# poseidon.net
KiCad netlist of a schematic drawn in EAGLE
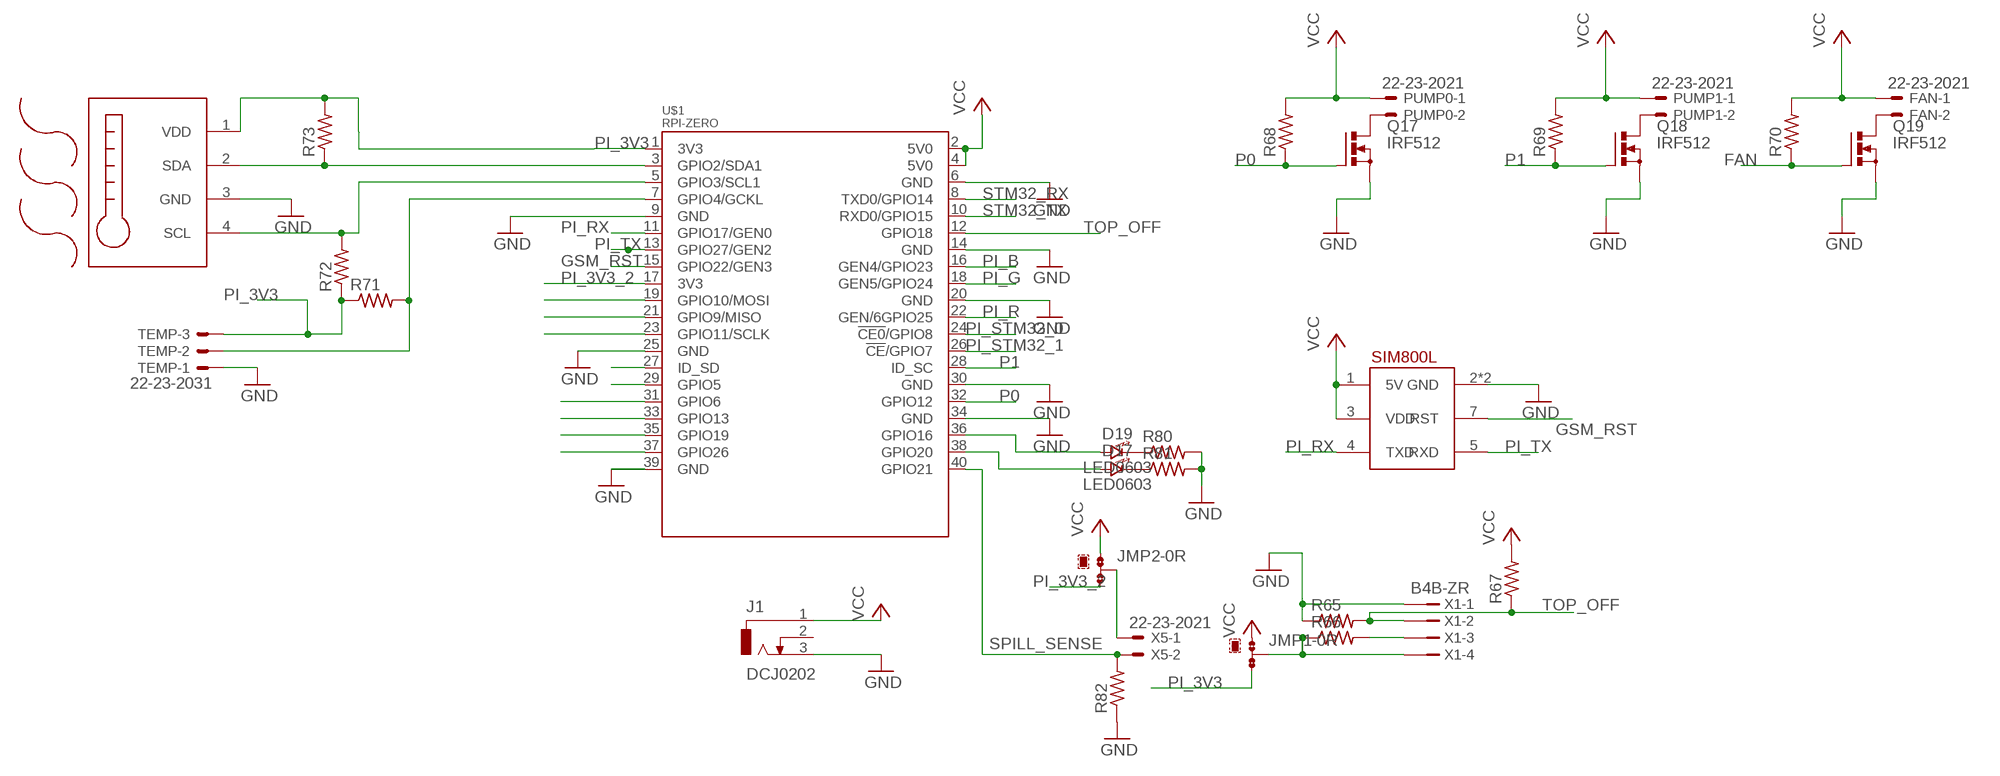
[diagram p0: schematic, sheet 1]
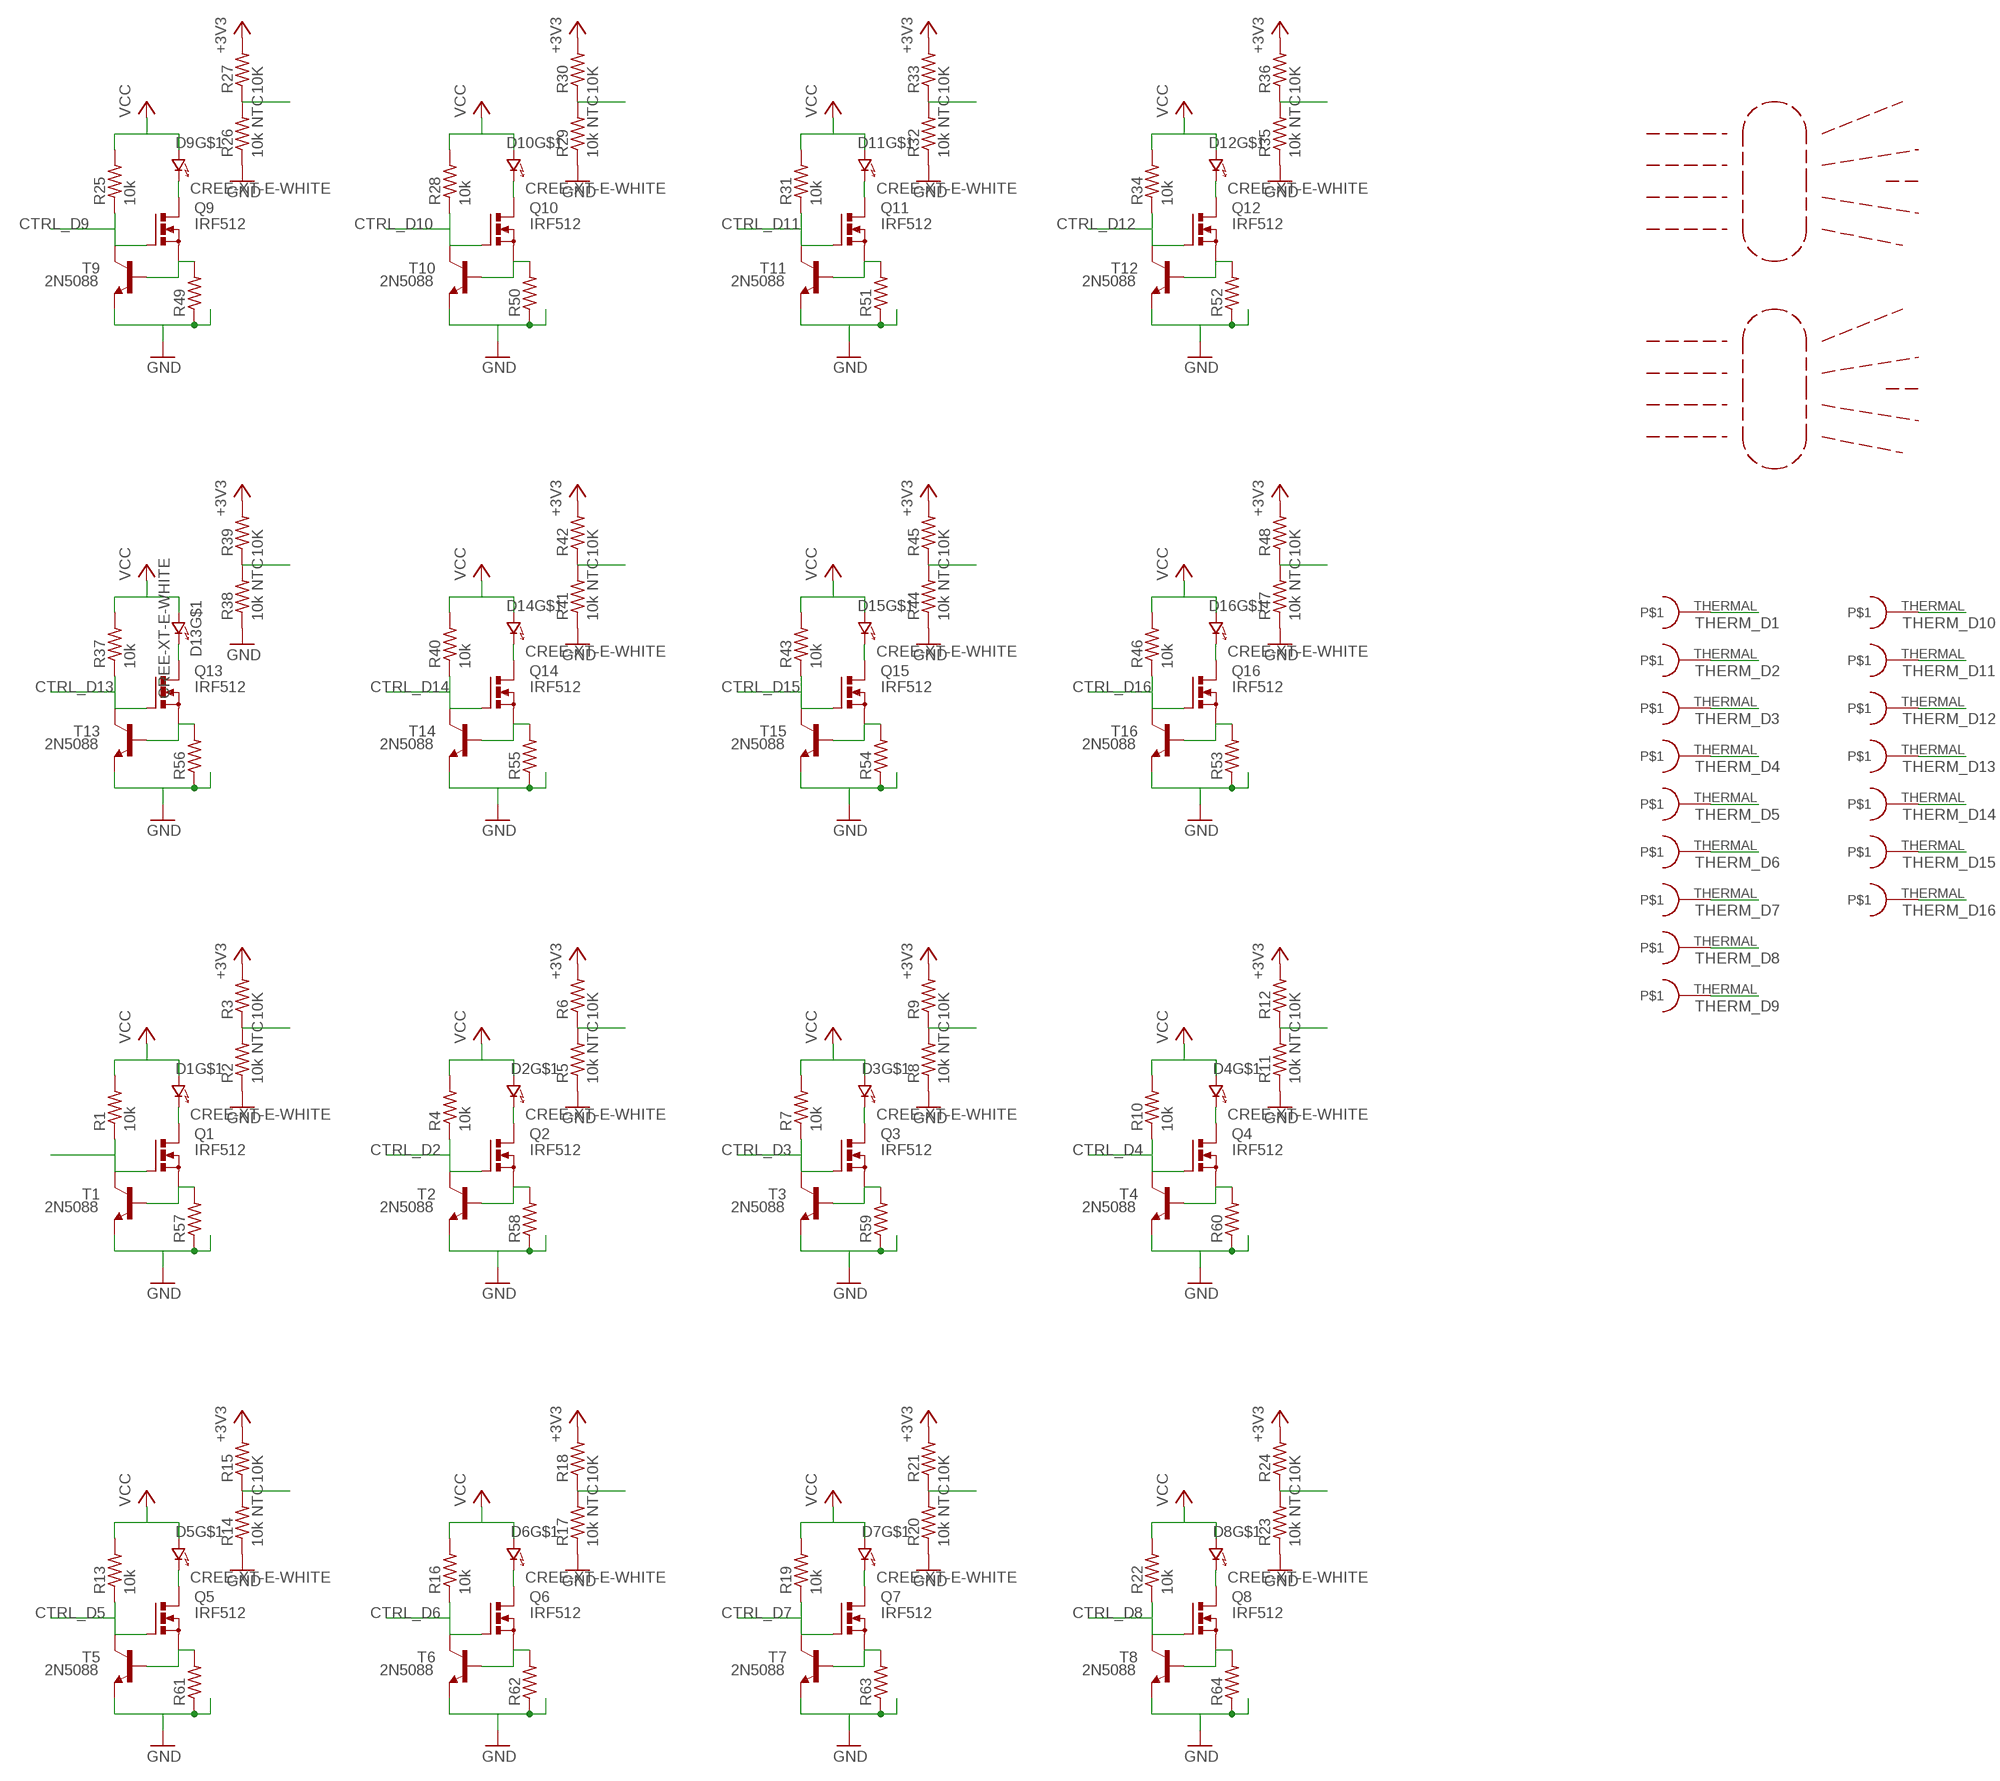
[diagram p1: schematic, sheet 2]
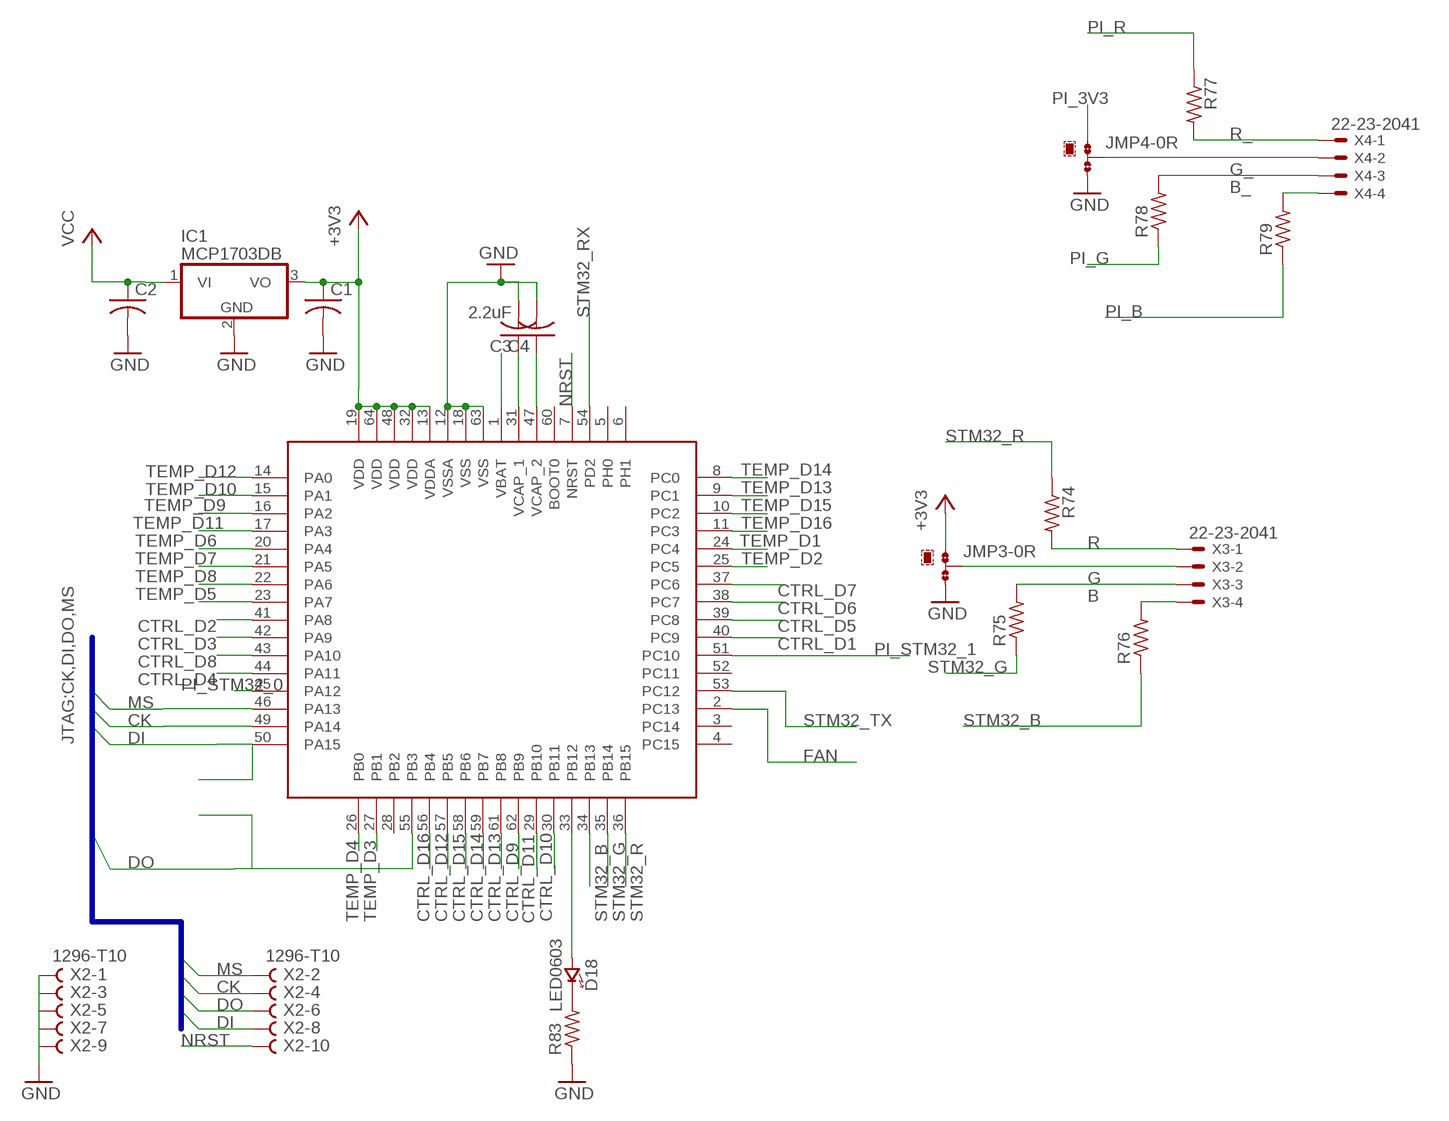
[diagram p2: schematic, sheet 3]

(export (version "E")
  (design (tool "Eeschema 10.0.6"))
  (components
    (comp (ref "C1")
      (value "C-USC0805")
      (footprint "eagle-import:C0805")
      (libsource (lib "eagle-import") (part "C-USC0805"))
    )
    (comp (ref "C2")
      (value "C-USC0805")
      (footprint "eagle-import:C0805")
      (libsource (lib "eagle-import") (part "C-USC0805"))
    )
    (comp (ref "C3")
      (value "2.2uF")
      (footprint "eagle-import:C0402K")
      (libsource (lib "eagle-import") (part "resistor_348_C-USC0402K"))
    )
    (comp (ref "C4")
      (value "C-USC0402K")
      (footprint "eagle-import:C0402K")
      (libsource (lib "eagle-import") (part "resistor_348_C-USC0402K"))
    )
    (comp (ref "D18")
      (value "LED0603")
      (footprint "eagle-import:LED-0603")
      (libsource (lib "eagle-import") (part "LED0603"))
    )
    (comp (ref "IC1")
      (value "MCP1703DB")
      (footprint "eagle-import:SOT223")
      (libsource (lib "eagle-import") (part "MCP1703DB"))
    )
    (comp (ref "JMP3")
      (value "0R-JUMPA")
      (footprint "eagle-import:A0R-JMP")
      (libsource (lib "eagle-import") (part "0R-JUMPA"))
    )
    (comp (ref "JMP4")
      (value "0R-JUMPA")
      (footprint "eagle-import:A0R-JMP")
      (libsource (lib "eagle-import") (part "0R-JUMPA"))
    )
    (comp (ref "R74")
      (value "R-US_R0805")
      (footprint "eagle-import:R0805")
      (libsource (lib "eagle-import") (part "resistor_348_R-US_R0805"))
    )
    (comp (ref "R75")
      (value "R-US_R0805")
      (footprint "eagle-import:R0805")
      (libsource (lib "eagle-import") (part "resistor_348_R-US_R0805"))
    )
    (comp (ref "R76")
      (value "R-US_R0805")
      (footprint "eagle-import:R0805")
      (libsource (lib "eagle-import") (part "resistor_348_R-US_R0805"))
    )
    (comp (ref "R77")
      (value "R-US_R0805")
      (footprint "eagle-import:R0805")
      (libsource (lib "eagle-import") (part "resistor_348_R-US_R0805"))
    )
    (comp (ref "R78")
      (value "R-US_R0805")
      (footprint "eagle-import:R0805")
      (libsource (lib "eagle-import") (part "resistor_348_R-US_R0805"))
    )
    (comp (ref "R79")
      (value "R-US_R0805")
      (footprint "eagle-import:R0805")
      (libsource (lib "eagle-import") (part "resistor_348_R-US_R0805"))
    )
    (comp (ref "R83")
      (value "R-US_R0805")
      (footprint "eagle-import:R0805")
      (libsource (lib "eagle-import") (part "resistor_348_R-US_R0805"))
    )
    (comp (ref "U$2")
      (value "STM32F41")
      (footprint "eagle-import:QFP50P1200X1200X160-64")
      (libsource (lib "eagle-import") (part "STM32F41"))
    )
    (comp (ref "X2")
      (value "1296-T10")
      (footprint "eagle-import:1296-10")
      (libsource (lib "eagle-import") (part "1296-T10"))
    )
    (comp (ref "X3")
      (value "22-23-2041")
      (footprint "eagle-import:22-23-2041")
      (fields (field (name "MF") "MOLEX"))
      (libsource (lib "eagle-import") (part "22-23-2041"))
    )
    (comp (ref "X4")
      (value "22-23-2041")
      (footprint "eagle-import:22-23-2041")
      (fields (field (name "MF") "MOLEX"))
      (libsource (lib "eagle-import") (part "22-23-2041"))
    )
    (comp (ref "D17")
      (value "LED0603")
      (footprint "eagle-import:LED-0603")
      (libsource (lib "eagle-import") (part "LED0603"))
    )
    (comp (ref "D19")
      (value "LED0603")
      (footprint "eagle-import:LED-0603")
      (libsource (lib "eagle-import") (part "LED0603"))
    )
    (comp (ref "FAN")
      (value "22-23-2021")
      (footprint "eagle-import:22-23-2021")
      (fields (field (name "MF") "MOLEX"))
      (libsource (lib "eagle-import") (part "22-23-2021"))
    )
    (comp (ref "J1")
      (value "DCJ0202")
      (footprint "eagle-import:DCJ0202")
      (libsource (lib "eagle-import") (part "DCJ0202"))
    )
    (comp (ref "JMP1")
      (value "0R-JUMPA")
      (footprint "eagle-import:A0R-JMP")
      (libsource (lib "eagle-import") (part "0R-JUMPA"))
    )
    (comp (ref "JMP2")
      (value "0R-JUMPA")
      (footprint "eagle-import:A0R-JMP")
      (libsource (lib "eagle-import") (part "0R-JUMPA"))
    )
    (comp (ref "PUMP0")
      (value "22-23-2021")
      (footprint "eagle-import:22-23-2021")
      (fields (field (name "MF") "MOLEX"))
      (libsource (lib "eagle-import") (part "22-23-2021"))
    )
    (comp (ref "PUMP1")
      (value "22-23-2021")
      (footprint "eagle-import:22-23-2021")
      (fields (field (name "MF") "MOLEX"))
      (libsource (lib "eagle-import") (part "22-23-2021"))
    )
    (comp (ref "Q17")
      (value "IRF512")
      (footprint "eagle-import:TO220BV")
      (libsource (lib "eagle-import") (part "IRF512"))
    )
    (comp (ref "Q18")
      (value "IRF512")
      (footprint "eagle-import:TO220BV")
      (libsource (lib "eagle-import") (part "IRF512"))
    )
    (comp (ref "Q19")
      (value "IRF512")
      (footprint "eagle-import:TO220BV")
      (libsource (lib "eagle-import") (part "IRF512"))
    )
    (comp (ref "R65")
      (value "R-US_R0805")
      (footprint "eagle-import:R0805")
      (libsource (lib "eagle-import") (part "resistor_348_R-US_R0805"))
    )
    (comp (ref "R66")
      (value "R-US_R0805")
      (footprint "eagle-import:R0805")
      (libsource (lib "eagle-import") (part "resistor_348_R-US_R0805"))
    )
    (comp (ref "R67")
      (value "R-US_M0805")
      (footprint "eagle-import:M0805")
      (libsource (lib "eagle-import") (part "resistor_348_R-US_M0805"))
    )
    (comp (ref "R68")
      (value "R-US_R0805")
      (footprint "eagle-import:R0805")
      (libsource (lib "eagle-import") (part "resistor_348_R-US_R0805"))
    )
    (comp (ref "R69")
      (value "R-US_R0805")
      (footprint "eagle-import:R0805")
      (libsource (lib "eagle-import") (part "resistor_348_R-US_R0805"))
    )
    (comp (ref "R70")
      (value "R-US_R0805")
      (footprint "eagle-import:R0805")
      (libsource (lib "eagle-import") (part "resistor_348_R-US_R0805"))
    )
    (comp (ref "R71")
      (value "R-US_R0805")
      (footprint "eagle-import:R0805")
      (libsource (lib "eagle-import") (part "R-US_R0805"))
    )
    (comp (ref "R72")
      (value "R-US_R0805")
      (footprint "eagle-import:R0805")
      (libsource (lib "eagle-import") (part "R-US_R0805"))
    )
    (comp (ref "R73")
      (value "R-US_R0805")
      (footprint "eagle-import:R0805")
      (libsource (lib "eagle-import") (part "R-US_R0805"))
    )
    (comp (ref "R80")
      (value "R-US_R0805")
      (footprint "eagle-import:R0805")
      (libsource (lib "eagle-import") (part "resistor_348_R-US_R0805"))
    )
    (comp (ref "R81")
      (value "R-US_R0805")
      (footprint "eagle-import:R0805")
      (libsource (lib "eagle-import") (part "resistor_348_R-US_R0805"))
    )
    (comp (ref "R82")
      (value "R-US_R0805")
      (footprint "eagle-import:R0805")
      (libsource (lib "eagle-import") (part "resistor_348_R-US_R0805"))
    )
    (comp (ref "TEMP")
      (value "22-23-2031")
      (footprint "eagle-import:22-23-2031")
      (fields (field (name "MF") "MOLEX"))
      (libsource (lib "eagle-import") (part "22-23-2031"))
    )
    (comp (ref "U$1")
      (value "RPI-ZERO")
      (footprint "eagle-import:RASPBERRYPI_BASTELSTUBE_V13_RASPI_BOARD_B+_FULL")
      (libsource (lib "eagle-import") (part "RPI-ZERO"))
    )
    (comp (ref "U$3")
      (value "AM2320")
      (footprint "eagle-import:4PIN_SMD")
      (libsource (lib "eagle-import") (part "AM2320"))
    )
    (comp (ref "U$21")
      (value "SIM800L")
      (footprint "eagle-import:SIP")
      (libsource (lib "eagle-import") (part "SIM800L"))
    )
    (comp (ref "X1")
      (value "B4B-ZR")
      (footprint "eagle-import:B4B-ZR")
      (fields (field (name "MF") "FARNELL") (field (name "MPN") "B4B-ZR(LF)(SN)"))
      (libsource (lib "eagle-import") (part "?4B-ZRB"))
    )
    (comp (ref "X5")
      (value "22-23-2021")
      (footprint "eagle-import:22-23-2021")
      (fields (field (name "MF") "MOLEX"))
      (libsource (lib "eagle-import") (part "22-23-2021"))
    )
    (comp (ref "D1")
      (value "CREE-XT-E-WHITE")
      (footprint "eagle-import:CREE-XT-E")
      (fields (field (name "MANUFACTURER") "Cree") (field (name "MPN") "XTEAWT-00-0000-000000G51"))
      (libsource (lib "eagle-import") (part "CREE-XT-E-WHITE"))
    )
    (comp (ref "D2")
      (value "CREE-XT-E-WHITE")
      (footprint "eagle-import:CREE-XT-E")
      (fields (field (name "MANUFACTURER") "Cree") (field (name "MPN") "XTEAWT-00-0000-000000G51"))
      (libsource (lib "eagle-import") (part "CREE-XT-E-WHITE"))
    )
    (comp (ref "D3")
      (value "CREE-XT-E-WHITE")
      (footprint "eagle-import:CREE-XT-E")
      (fields (field (name "MANUFACTURER") "Cree") (field (name "MPN") "XTEAWT-00-0000-000000G51"))
      (libsource (lib "eagle-import") (part "CREE-XT-E-WHITE"))
    )
    (comp (ref "D4")
      (value "CREE-XT-E-WHITE")
      (footprint "eagle-import:CREE-XT-E")
      (fields (field (name "MANUFACTURER") "Cree") (field (name "MPN") "XTEAWT-00-0000-000000G51"))
      (libsource (lib "eagle-import") (part "CREE-XT-E-WHITE"))
    )
    (comp (ref "D5")
      (value "CREE-XT-E-WHITE")
      (footprint "eagle-import:CREE-XT-E")
      (fields (field (name "MANUFACTURER") "Cree") (field (name "MPN") "XTEAWT-00-0000-000000G51"))
      (libsource (lib "eagle-import") (part "CREE-XT-E-WHITE"))
    )
    (comp (ref "D6")
      (value "CREE-XT-E-WHITE")
      (footprint "eagle-import:CREE-XT-E")
      (fields (field (name "MANUFACTURER") "Cree") (field (name "MPN") "XTEAWT-00-0000-000000G51"))
      (libsource (lib "eagle-import") (part "CREE-XT-E-WHITE"))
    )
    (comp (ref "D7")
      (value "CREE-XT-E-WHITE")
      (footprint "eagle-import:CREE-XT-E")
      (fields (field (name "MANUFACTURER") "Cree") (field (name "MPN") "XTEAWT-00-0000-000000G51"))
      (libsource (lib "eagle-import") (part "CREE-XT-E-WHITE"))
    )
    (comp (ref "D8")
      (value "CREE-XT-E-WHITE")
      (footprint "eagle-import:CREE-XT-E")
      (fields (field (name "MANUFACTURER") "Cree") (field (name "MPN") "XTEAWT-00-0000-000000G51"))
      (libsource (lib "eagle-import") (part "CREE-XT-E-WHITE"))
    )
    (comp (ref "D9")
      (value "CREE-XT-E-WHITE")
      (footprint "eagle-import:CREE-XT-E")
      (fields (field (name "MANUFACTURER") "Cree") (field (name "MPN") "XTEAWT-00-0000-000000G51"))
      (libsource (lib "eagle-import") (part "CREE-XT-E-WHITE"))
    )
    (comp (ref "D10")
      (value "CREE-XT-E-WHITE")
      (footprint "eagle-import:CREE-XT-E")
      (fields (field (name "MANUFACTURER") "Cree") (field (name "MPN") "XTEAWT-00-0000-000000G51"))
      (libsource (lib "eagle-import") (part "CREE-XT-E-WHITE"))
    )
    (comp (ref "D11")
      (value "CREE-XT-E-WHITE")
      (footprint "eagle-import:CREE-XT-E")
      (fields (field (name "MANUFACTURER") "Cree") (field (name "MPN") "XTEAWT-00-0000-000000G51"))
      (libsource (lib "eagle-import") (part "CREE-XT-E-WHITE"))
    )
    (comp (ref "D12")
      (value "CREE-XT-E-WHITE")
      (footprint "eagle-import:CREE-XT-E")
      (fields (field (name "MANUFACTURER") "Cree") (field (name "MPN") "XTEAWT-00-0000-000000G51"))
      (libsource (lib "eagle-import") (part "CREE-XT-E-WHITE"))
    )
    (comp (ref "D13")
      (value "CREE-XT-E-WHITE")
      (footprint "eagle-import:CREE-XT-E")
      (fields (field (name "MANUFACTURER") "Cree") (field (name "MPN") "XTEAWT-00-0000-000000G51"))
      (libsource (lib "eagle-import") (part "CREE-XT-E-WHITE"))
    )
    (comp (ref "D14")
      (value "CREE-XT-E-WHITE")
      (footprint "eagle-import:CREE-XT-E")
      (fields (field (name "MANUFACTURER") "Cree") (field (name "MPN") "XTEAWT-00-0000-000000G51"))
      (libsource (lib "eagle-import") (part "CREE-XT-E-WHITE"))
    )
    (comp (ref "D15")
      (value "CREE-XT-E-WHITE")
      (footprint "eagle-import:CREE-XT-E")
      (fields (field (name "MANUFACTURER") "Cree") (field (name "MPN") "XTEAWT-00-0000-000000G51"))
      (libsource (lib "eagle-import") (part "CREE-XT-E-WHITE"))
    )
    (comp (ref "D16")
      (value "CREE-XT-E-WHITE")
      (footprint "eagle-import:CREE-XT-E")
      (fields (field (name "MANUFACTURER") "Cree") (field (name "MPN") "XTEAWT-00-0000-000000G51"))
      (libsource (lib "eagle-import") (part "CREE-XT-E-WHITE"))
    )
    (comp (ref "Q1")
      (value "IRF512")
      (footprint "eagle-import:TO220BV")
      (libsource (lib "eagle-import") (part "IRF512"))
    )
    (comp (ref "Q2")
      (value "IRF512")
      (footprint "eagle-import:TO220BV")
      (libsource (lib "eagle-import") (part "IRF512"))
    )
    (comp (ref "Q3")
      (value "IRF512")
      (footprint "eagle-import:TO220BV")
      (libsource (lib "eagle-import") (part "IRF512"))
    )
    (comp (ref "Q4")
      (value "IRF512")
      (footprint "eagle-import:TO220BV")
      (libsource (lib "eagle-import") (part "IRF512"))
    )
    (comp (ref "Q5")
      (value "IRF512")
      (footprint "eagle-import:TO220BV")
      (libsource (lib "eagle-import") (part "IRF512"))
    )
    (comp (ref "Q6")
      (value "IRF512")
      (footprint "eagle-import:TO220BV")
      (libsource (lib "eagle-import") (part "IRF512"))
    )
    (comp (ref "Q7")
      (value "IRF512")
      (footprint "eagle-import:TO220BV")
      (libsource (lib "eagle-import") (part "IRF512"))
    )
    (comp (ref "Q8")
      (value "IRF512")
      (footprint "eagle-import:TO220BV")
      (libsource (lib "eagle-import") (part "IRF512"))
    )
    (comp (ref "Q9")
      (value "IRF512")
      (footprint "eagle-import:TO220BV")
      (libsource (lib "eagle-import") (part "IRF512"))
    )
    (comp (ref "Q10")
      (value "IRF512")
      (footprint "eagle-import:TO220BV")
      (libsource (lib "eagle-import") (part "IRF512"))
    )
    (comp (ref "Q11")
      (value "IRF512")
      (footprint "eagle-import:TO220BV")
      (libsource (lib "eagle-import") (part "IRF512"))
    )
    (comp (ref "Q12")
      (value "IRF512")
      (footprint "eagle-import:TO220BV")
      (libsource (lib "eagle-import") (part "IRF512"))
    )
    (comp (ref "Q13")
      (value "IRF512")
      (footprint "eagle-import:TO220BV")
      (libsource (lib "eagle-import") (part "IRF512"))
    )
    (comp (ref "Q14")
      (value "IRF512")
      (footprint "eagle-import:TO220BV")
      (libsource (lib "eagle-import") (part "IRF512"))
    )
    (comp (ref "Q15")
      (value "IRF512")
      (footprint "eagle-import:TO220BV")
      (libsource (lib "eagle-import") (part "IRF512"))
    )
    (comp (ref "Q16")
      (value "IRF512")
      (footprint "eagle-import:TO220BV")
      (libsource (lib "eagle-import") (part "IRF512"))
    )
    (comp (ref "R1")
      (value "10k")
      (footprint "eagle-import:R0805")
      (libsource (lib "eagle-import") (part "R-US_R0805"))
    )
    (comp (ref "R2")
      (value "10k NTC")
      (footprint "eagle-import:R0805")
      (libsource (lib "eagle-import") (part "R-US_R0805"))
    )
    (comp (ref "R3")
      (value "10K")
      (footprint "eagle-import:R0603")
      (libsource (lib "eagle-import") (part "R-US_R0603"))
    )
    (comp (ref "R4")
      (value "10k")
      (footprint "eagle-import:R0805")
      (libsource (lib "eagle-import") (part "R-US_R0805"))
    )
    (comp (ref "R5")
      (value "10k NTC")
      (footprint "eagle-import:R0805")
      (libsource (lib "eagle-import") (part "R-US_R0805"))
    )
    (comp (ref "R6")
      (value "10K")
      (footprint "eagle-import:R0603")
      (libsource (lib "eagle-import") (part "R-US_R0603"))
    )
    (comp (ref "R7")
      (value "10k")
      (footprint "eagle-import:R0805")
      (libsource (lib "eagle-import") (part "R-US_R0805"))
    )
    (comp (ref "R8")
      (value "10k NTC")
      (footprint "eagle-import:R0805")
      (libsource (lib "eagle-import") (part "R-US_R0805"))
    )
    (comp (ref "R9")
      (value "10K")
      (footprint "eagle-import:R0603")
      (libsource (lib "eagle-import") (part "R-US_R0603"))
    )
    (comp (ref "R10")
      (value "10k")
      (footprint "eagle-import:R0805")
      (libsource (lib "eagle-import") (part "R-US_R0805"))
    )
    (comp (ref "R11")
      (value "10k NTC")
      (footprint "eagle-import:R0805")
      (libsource (lib "eagle-import") (part "R-US_R0805"))
    )
    (comp (ref "R12")
      (value "10K")
      (footprint "eagle-import:R0603")
      (libsource (lib "eagle-import") (part "R-US_R0603"))
    )
    (comp (ref "R13")
      (value "10k")
      (footprint "eagle-import:R0805")
      (libsource (lib "eagle-import") (part "R-US_R0805"))
    )
    (comp (ref "R14")
      (value "10k NTC")
      (footprint "eagle-import:R0805")
      (libsource (lib "eagle-import") (part "R-US_R0805"))
    )
    (comp (ref "R15")
      (value "10K")
      (footprint "eagle-import:R0603")
      (libsource (lib "eagle-import") (part "R-US_R0603"))
    )
    (comp (ref "R16")
      (value "10k")
      (footprint "eagle-import:R0805")
      (libsource (lib "eagle-import") (part "R-US_R0805"))
    )
    (comp (ref "R17")
      (value "10k NTC")
      (footprint "eagle-import:R0805")
      (libsource (lib "eagle-import") (part "R-US_R0805"))
    )
    (comp (ref "R18")
      (value "10K")
      (footprint "eagle-import:R0603")
      (libsource (lib "eagle-import") (part "R-US_R0603"))
    )
    (comp (ref "R19")
      (value "10k")
      (footprint "eagle-import:R0805")
      (libsource (lib "eagle-import") (part "R-US_R0805"))
    )
    (comp (ref "R20")
      (value "10k NTC")
      (footprint "eagle-import:R0805")
      (libsource (lib "eagle-import") (part "R-US_R0805"))
    )
    (comp (ref "R21")
      (value "10K")
      (footprint "eagle-import:R0603")
      (libsource (lib "eagle-import") (part "R-US_R0603"))
    )
    (comp (ref "R22")
      (value "10k")
      (footprint "eagle-import:R0805")
      (libsource (lib "eagle-import") (part "R-US_R0805"))
    )
    (comp (ref "R23")
      (value "10k NTC")
      (footprint "eagle-import:R0805")
      (libsource (lib "eagle-import") (part "R-US_R0805"))
    )
    (comp (ref "R24")
      (value "10K")
      (footprint "eagle-import:R0603")
      (libsource (lib "eagle-import") (part "R-US_R0603"))
    )
    (comp (ref "R25")
      (value "10k")
      (footprint "eagle-import:R0805")
      (libsource (lib "eagle-import") (part "R-US_R0805"))
    )
    (comp (ref "R26")
      (value "10k NTC")
      (footprint "eagle-import:R0805")
      (libsource (lib "eagle-import") (part "R-US_R0805"))
    )
    (comp (ref "R27")
      (value "10K")
      (footprint "eagle-import:R0603")
      (libsource (lib "eagle-import") (part "R-US_R0603"))
    )
    (comp (ref "R28")
      (value "10k")
      (footprint "eagle-import:R0805")
      (libsource (lib "eagle-import") (part "R-US_R0805"))
    )
    (comp (ref "R29")
      (value "10k NTC")
      (footprint "eagle-import:R0805")
      (libsource (lib "eagle-import") (part "R-US_R0805"))
    )
    (comp (ref "R30")
      (value "10K")
      (footprint "eagle-import:R0603")
      (libsource (lib "eagle-import") (part "R-US_R0603"))
    )
    (comp (ref "R31")
      (value "10k")
      (footprint "eagle-import:R0805")
      (libsource (lib "eagle-import") (part "R-US_R0805"))
    )
    (comp (ref "R32")
      (value "10k NTC")
      (footprint "eagle-import:R0805")
      (libsource (lib "eagle-import") (part "R-US_R0805"))
    )
    (comp (ref "R33")
      (value "10K")
      (footprint "eagle-import:R0603")
      (libsource (lib "eagle-import") (part "R-US_R0603"))
    )
    (comp (ref "R34")
      (value "10k")
      (footprint "eagle-import:R0805")
      (libsource (lib "eagle-import") (part "R-US_R0805"))
    )
    (comp (ref "R35")
      (value "10k NTC")
      (footprint "eagle-import:R0805")
      (libsource (lib "eagle-import") (part "R-US_R0805"))
    )
    (comp (ref "R36")
      (value "10K")
      (footprint "eagle-import:R0603")
      (libsource (lib "eagle-import") (part "R-US_R0603"))
    )
    (comp (ref "R37")
      (value "10k")
      (footprint "eagle-import:R0805")
      (libsource (lib "eagle-import") (part "R-US_R0805"))
    )
    (comp (ref "R38")
      (value "10k NTC")
      (footprint "eagle-import:R0805")
      (libsource (lib "eagle-import") (part "R-US_R0805"))
    )
    (comp (ref "R39")
      (value "10K")
      (footprint "eagle-import:R0603")
      (libsource (lib "eagle-import") (part "R-US_R0603"))
    )
    (comp (ref "R40")
      (value "10k")
      (footprint "eagle-import:R0805")
      (libsource (lib "eagle-import") (part "R-US_R0805"))
    )
    (comp (ref "R41")
      (value "10k NTC")
      (footprint "eagle-import:R0805")
      (libsource (lib "eagle-import") (part "R-US_R0805"))
    )
    (comp (ref "R42")
      (value "10K")
      (footprint "eagle-import:R0603")
      (libsource (lib "eagle-import") (part "R-US_R0603"))
    )
    (comp (ref "R43")
      (value "10k")
      (footprint "eagle-import:R0805")
      (libsource (lib "eagle-import") (part "R-US_R0805"))
    )
    (comp (ref "R44")
      (value "10k NTC")
      (footprint "eagle-import:R0805")
      (libsource (lib "eagle-import") (part "R-US_R0805"))
    )
    (comp (ref "R45")
      (value "10K")
      (footprint "eagle-import:R0603")
      (libsource (lib "eagle-import") (part "R-US_R0603"))
    )
    (comp (ref "R46")
      (value "10k")
      (footprint "eagle-import:R0805")
      (libsource (lib "eagle-import") (part "R-US_R0805"))
    )
    (comp (ref "R47")
      (value "10k NTC")
      (footprint "eagle-import:R0805")
      (libsource (lib "eagle-import") (part "R-US_R0805"))
    )
    (comp (ref "R48")
      (value "10K")
      (footprint "eagle-import:R0603")
      (libsource (lib "eagle-import") (part "R-US_R0603"))
    )
    (comp (ref "R49")
      (value "R-US_R2512")
      (footprint "eagle-import:R2512")
      (libsource (lib "eagle-import") (part "R-US_R2512"))
    )
    (comp (ref "R50")
      (value "R-US_R2512")
      (footprint "eagle-import:R2512")
      (libsource (lib "eagle-import") (part "R-US_R2512"))
    )
    (comp (ref "R51")
      (value "R-US_R2512")
      (footprint "eagle-import:R2512")
      (libsource (lib "eagle-import") (part "R-US_R2512"))
    )
    (comp (ref "R52")
      (value "R-US_R2512")
      (footprint "eagle-import:R2512")
      (libsource (lib "eagle-import") (part "R-US_R2512"))
    )
    (comp (ref "R53")
      (value "R-US_R2512")
      (footprint "eagle-import:R2512")
      (libsource (lib "eagle-import") (part "R-US_R2512"))
    )
    (comp (ref "R54")
      (value "R-US_R2512")
      (footprint "eagle-import:R2512")
      (libsource (lib "eagle-import") (part "R-US_R2512"))
    )
    (comp (ref "R55")
      (value "R-US_R2512")
      (footprint "eagle-import:R2512")
      (libsource (lib "eagle-import") (part "R-US_R2512"))
    )
    (comp (ref "R56")
      (value "R-US_R2512")
      (footprint "eagle-import:R2512")
      (libsource (lib "eagle-import") (part "R-US_R2512"))
    )
    (comp (ref "R57")
      (value "R-US_R2512")
      (footprint "eagle-import:R2512")
      (libsource (lib "eagle-import") (part "R-US_R2512"))
    )
    (comp (ref "R58")
      (value "R-US_R2512")
      (footprint "eagle-import:R2512")
      (libsource (lib "eagle-import") (part "R-US_R2512"))
    )
    (comp (ref "R59")
      (value "R-US_R2512")
      (footprint "eagle-import:R2512")
      (libsource (lib "eagle-import") (part "R-US_R2512"))
    )
    (comp (ref "R60")
      (value "R-US_R2512")
      (footprint "eagle-import:R2512")
      (libsource (lib "eagle-import") (part "R-US_R2512"))
    )
    (comp (ref "R61")
      (value "R-US_R2512")
      (footprint "eagle-import:R2512")
      (libsource (lib "eagle-import") (part "R-US_R2512"))
    )
    (comp (ref "R62")
      (value "R-US_R2512")
      (footprint "eagle-import:R2512")
      (libsource (lib "eagle-import") (part "R-US_R2512"))
    )
    (comp (ref "R63")
      (value "R-US_R2512")
      (footprint "eagle-import:R2512")
      (libsource (lib "eagle-import") (part "R-US_R2512"))
    )
    (comp (ref "R64")
      (value "R-US_R2512")
      (footprint "eagle-import:R2512")
      (libsource (lib "eagle-import") (part "R-US_R2512"))
    )
    (comp (ref "T1")
      (value "2N5088")
      (footprint "eagle-import:TO92")
      (libsource (lib "eagle-import") (part "2N5088"))
    )
    (comp (ref "T2")
      (value "2N5088")
      (footprint "eagle-import:TO92")
      (libsource (lib "eagle-import") (part "2N5088"))
    )
    (comp (ref "T3")
      (value "2N5088")
      (footprint "eagle-import:TO92")
      (libsource (lib "eagle-import") (part "2N5088"))
    )
    (comp (ref "T4")
      (value "2N5088")
      (footprint "eagle-import:TO92")
      (libsource (lib "eagle-import") (part "2N5088"))
    )
    (comp (ref "T5")
      (value "2N5088")
      (footprint "eagle-import:TO92")
      (libsource (lib "eagle-import") (part "2N5088"))
    )
    (comp (ref "T6")
      (value "2N5088")
      (footprint "eagle-import:TO92")
      (libsource (lib "eagle-import") (part "2N5088"))
    )
    (comp (ref "T7")
      (value "2N5088")
      (footprint "eagle-import:TO92")
      (libsource (lib "eagle-import") (part "2N5088"))
    )
    (comp (ref "T8")
      (value "2N5088")
      (footprint "eagle-import:TO92")
      (libsource (lib "eagle-import") (part "2N5088"))
    )
    (comp (ref "T9")
      (value "2N5088")
      (footprint "eagle-import:TO92")
      (libsource (lib "eagle-import") (part "2N5088"))
    )
    (comp (ref "T10")
      (value "2N5088")
      (footprint "eagle-import:TO92")
      (libsource (lib "eagle-import") (part "2N5088"))
    )
    (comp (ref "T11")
      (value "2N5088")
      (footprint "eagle-import:TO92")
      (libsource (lib "eagle-import") (part "2N5088"))
    )
    (comp (ref "T12")
      (value "2N5088")
      (footprint "eagle-import:TO92")
      (libsource (lib "eagle-import") (part "2N5088"))
    )
    (comp (ref "T13")
      (value "2N5088")
      (footprint "eagle-import:TO92")
      (libsource (lib "eagle-import") (part "2N5088"))
    )
    (comp (ref "T14")
      (value "2N5088")
      (footprint "eagle-import:TO92")
      (libsource (lib "eagle-import") (part "2N5088"))
    )
    (comp (ref "T15")
      (value "2N5088")
      (footprint "eagle-import:TO92")
      (libsource (lib "eagle-import") (part "2N5088"))
    )
    (comp (ref "T16")
      (value "2N5088")
      (footprint "eagle-import:TO92")
      (libsource (lib "eagle-import") (part "2N5088"))
    )
    (comp (ref "U$19")
      (value "8X_LED_OPTIC")
      (footprint "eagle-import:FOCUS_GRID")
      (libsource (lib "eagle-import") (part "8X_LED_OPTIC"))
    )
    (comp (ref "U$20")
      (value "8X_LED_OPTIC")
      (footprint "eagle-import:FOCUS_GRID")
      (libsource (lib "eagle-import") (part "8X_LED_OPTIC"))
    )
  )
  (nets
    (net (code "2") (name "+3V3") (class "Default")
      (node (ref "C1") (pin "1") (pinfunction "1_1") (pintype "passive"))
      (node (ref "IC1") (pin "3") (pinfunction "VO_3") (pintype "passive"))
      (node (ref "JMP3") (pin "1") (pinfunction "1_1") (pintype "passive"))
      (node (ref "R12") (pin "2") (pinfunction "2_2") (pintype "passive"))
      (node (ref "R15") (pin "2") (pinfunction "2_2") (pintype "passive"))
      (node (ref "R18") (pin "2") (pinfunction "2_2") (pintype "passive"))
      (node (ref "R21") (pin "2") (pinfunction "2_2") (pintype "passive"))
      (node (ref "R24") (pin "2") (pinfunction "2_2") (pintype "passive"))
      (node (ref "R27") (pin "2") (pinfunction "2_2") (pintype "passive"))
      (node (ref "R3") (pin "2") (pinfunction "2_2") (pintype "passive"))
      (node (ref "R30") (pin "2") (pinfunction "2_2") (pintype "passive"))
      (node (ref "R33") (pin "2") (pinfunction "2_2") (pintype "passive"))
      (node (ref "R36") (pin "2") (pinfunction "2_2") (pintype "passive"))
      (node (ref "R39") (pin "2") (pinfunction "2_2") (pintype "passive"))
      (node (ref "R42") (pin "2") (pinfunction "2_2") (pintype "passive"))
      (node (ref "R45") (pin "2") (pinfunction "2_2") (pintype "passive"))
      (node (ref "R48") (pin "2") (pinfunction "2_2") (pintype "passive"))
      (node (ref "R6") (pin "2") (pinfunction "2_2") (pintype "passive"))
      (node (ref "R9") (pin "2") (pinfunction "2_2") (pintype "passive"))
      (node (ref "U$2") (pin "13") (pinfunction "VDDA_13") (pintype "bidirectional"))
      (node (ref "U$2") (pin "19") (pinfunction "VDD_19") (pintype "bidirectional"))
      (node (ref "U$2") (pin "32") (pinfunction "VDD_32") (pintype "bidirectional"))
      (node (ref "U$2") (pin "48") (pinfunction "VDD_48") (pintype "bidirectional"))
      (node (ref "U$2") (pin "64") (pinfunction "VDD_64") (pintype "bidirectional"))
    )
    (net (code "4") (name "B") (class "Default")
      (node (ref "R76") (pin "2") (pinfunction "2_2") (pintype "passive"))
      (node (ref "X3") (pin "4") (pinfunction "S_4") (pintype "passive"))
    )
    (net (code "5") (name "B_") (class "Default")
      (node (ref "R79") (pin "2") (pinfunction "2_2") (pintype "passive"))
      (node (ref "X4") (pin "4") (pinfunction "S_4") (pintype "passive"))
    )
    (net (code "6") (name "CK") (class "Default")
      (node (ref "U$2") (pin "49") (pinfunction "PA14_49") (pintype "bidirectional"))
      (node (ref "X2") (pin "4") (pinfunction "B_4") (pintype "passive"))
    )
    (net (code "7") (name "CTRL_D1") (class "Default")
      (node (ref "Q1") (pin "G") (pinfunction "G_G") (pintype "passive"))
      (node (ref "R1") (pin "1") (pinfunction "1_1") (pintype "passive"))
      (node (ref "T1") (pin "1") (pinfunction "C_1") (pintype "passive"))
      (node (ref "U$2") (pin "40") (pinfunction "PC9_40") (pintype "bidirectional"))
    )
    (net (code "8") (name "CTRL_D2") (class "Default")
      (node (ref "Q2") (pin "G") (pinfunction "G_G") (pintype "passive"))
      (node (ref "R4") (pin "1") (pinfunction "1_1") (pintype "passive"))
      (node (ref "T2") (pin "1") (pinfunction "C_1") (pintype "passive"))
      (node (ref "U$2") (pin "41") (pinfunction "PA8_41") (pintype "bidirectional"))
    )
    (net (code "9") (name "CTRL_D3") (class "Default")
      (node (ref "Q3") (pin "G") (pinfunction "G_G") (pintype "passive"))
      (node (ref "R7") (pin "1") (pinfunction "1_1") (pintype "passive"))
      (node (ref "T3") (pin "1") (pinfunction "C_1") (pintype "passive"))
      (node (ref "U$2") (pin "42") (pinfunction "PA9_42") (pintype "bidirectional"))
    )
    (net (code "10") (name "CTRL_D4") (class "Default")
      (node (ref "Q4") (pin "G") (pinfunction "G_G") (pintype "passive"))
      (node (ref "R10") (pin "1") (pinfunction "1_1") (pintype "passive"))
      (node (ref "T4") (pin "1") (pinfunction "C_1") (pintype "passive"))
      (node (ref "U$2") (pin "44") (pinfunction "PA11_44") (pintype "bidirectional"))
    )
    (net (code "11") (name "CTRL_D5") (class "Default")
      (node (ref "Q5") (pin "G") (pinfunction "G_G") (pintype "passive"))
      (node (ref "R13") (pin "1") (pinfunction "1_1") (pintype "passive"))
      (node (ref "T5") (pin "1") (pinfunction "C_1") (pintype "passive"))
      (node (ref "U$2") (pin "39") (pinfunction "PC8_39") (pintype "bidirectional"))
    )
    (net (code "12") (name "CTRL_D6") (class "Default")
      (node (ref "Q6") (pin "G") (pinfunction "G_G") (pintype "passive"))
      (node (ref "R16") (pin "1") (pinfunction "1_1") (pintype "passive"))
      (node (ref "T6") (pin "1") (pinfunction "C_1") (pintype "passive"))
      (node (ref "U$2") (pin "38") (pinfunction "PC7_38") (pintype "bidirectional"))
    )
    (net (code "13") (name "CTRL_D7") (class "Default")
      (node (ref "Q7") (pin "G") (pinfunction "G_G") (pintype "passive"))
      (node (ref "R19") (pin "1") (pinfunction "1_1") (pintype "passive"))
      (node (ref "T7") (pin "1") (pinfunction "C_1") (pintype "passive"))
      (node (ref "U$2") (pin "37") (pinfunction "PC6_37") (pintype "bidirectional"))
    )
    (net (code "14") (name "CTRL_D8") (class "Default")
      (node (ref "Q8") (pin "G") (pinfunction "G_G") (pintype "passive"))
      (node (ref "R22") (pin "1") (pinfunction "1_1") (pintype "passive"))
      (node (ref "T8") (pin "1") (pinfunction "C_1") (pintype "passive"))
      (node (ref "U$2") (pin "43") (pinfunction "PA10_43") (pintype "bidirectional"))
    )
    (net (code "15") (name "CTRL_D9") (class "Default")
      (node (ref "Q9") (pin "G") (pinfunction "G_G") (pintype "passive"))
      (node (ref "R25") (pin "1") (pinfunction "1_1") (pintype "passive"))
      (node (ref "T9") (pin "1") (pinfunction "C_1") (pintype "passive"))
      (node (ref "U$2") (pin "62") (pinfunction "PB9_62") (pintype "bidirectional"))
    )
    (net (code "16") (name "CTRL_D10") (class "Default")
      (node (ref "Q10") (pin "G") (pinfunction "G_G") (pintype "passive"))
      (node (ref "R28") (pin "1") (pinfunction "1_1") (pintype "passive"))
      (node (ref "T10") (pin "1") (pinfunction "C_1") (pintype "passive"))
      (node (ref "U$2") (pin "30") (pinfunction "PB11_30") (pintype "bidirectional"))
    )
    (net (code "17") (name "CTRL_D11") (class "Default")
      (node (ref "Q11") (pin "G") (pinfunction "G_G") (pintype "passive"))
      (node (ref "R31") (pin "1") (pinfunction "1_1") (pintype "passive"))
      (node (ref "T11") (pin "1") (pinfunction "C_1") (pintype "passive"))
      (node (ref "U$2") (pin "29") (pinfunction "PB10_29") (pintype "bidirectional"))
    )
    (net (code "18") (name "CTRL_D12") (class "Default")
      (node (ref "Q12") (pin "G") (pinfunction "G_G") (pintype "passive"))
      (node (ref "R34") (pin "1") (pinfunction "1_1") (pintype "passive"))
      (node (ref "T12") (pin "1") (pinfunction "C_1") (pintype "passive"))
      (node (ref "U$2") (pin "57") (pinfunction "PB5_57") (pintype "bidirectional"))
    )
    (net (code "19") (name "CTRL_D13") (class "Default")
      (node (ref "Q13") (pin "G") (pinfunction "G_G") (pintype "passive"))
      (node (ref "R37") (pin "1") (pinfunction "1_1") (pintype "passive"))
      (node (ref "T13") (pin "1") (pinfunction "C_1") (pintype "passive"))
      (node (ref "U$2") (pin "61") (pinfunction "PB8_61") (pintype "bidirectional"))
    )
    (net (code "20") (name "CTRL_D14") (class "Default")
      (node (ref "Q14") (pin "G") (pinfunction "G_G") (pintype "passive"))
      (node (ref "R40") (pin "1") (pinfunction "1_1") (pintype "passive"))
      (node (ref "T14") (pin "1") (pinfunction "C_1") (pintype "passive"))
      (node (ref "U$2") (pin "59") (pinfunction "PB7_59") (pintype "bidirectional"))
    )
    (net (code "21") (name "CTRL_D15") (class "Default")
      (node (ref "Q15") (pin "G") (pinfunction "G_G") (pintype "passive"))
      (node (ref "R43") (pin "1") (pinfunction "1_1") (pintype "passive"))
      (node (ref "T15") (pin "1") (pinfunction "C_1") (pintype "passive"))
      (node (ref "U$2") (pin "58") (pinfunction "PB6_58") (pintype "bidirectional"))
    )
    (net (code "22") (name "CTRL_D16") (class "Default")
      (node (ref "Q16") (pin "G") (pinfunction "G_G") (pintype "passive"))
      (node (ref "R46") (pin "1") (pinfunction "1_1") (pintype "passive"))
      (node (ref "T16") (pin "1") (pinfunction "C_1") (pintype "passive"))
      (node (ref "U$2") (pin "56") (pinfunction "PB4_56") (pintype "bidirectional"))
    )
    (net (code "23") (name "DI") (class "Default")
      (node (ref "U$2") (pin "50") (pinfunction "PA15_50") (pintype "bidirectional"))
      (node (ref "X2") (pin "8") (pinfunction "B_8") (pintype "passive"))
    )
    (net (code "24") (name "DO") (class "Default")
      (node (ref "U$2") (pin "55") (pinfunction "PB3_55") (pintype "bidirectional"))
      (node (ref "X2") (pin "6") (pinfunction "B_6") (pintype "passive"))
    )
    (net (code "25") (name "FAN") (class "Default")
      (node (ref "Q19") (pin "G") (pinfunction "G_G") (pintype "passive"))
      (node (ref "R70") (pin "1") (pinfunction "1_1") (pintype "passive"))
      (node (ref "U$2") (pin "2") (pinfunction "PC13_2") (pintype "bidirectional"))
    )
    (net (code "26") (name "G") (class "Default")
      (node (ref "R75") (pin "2") (pinfunction "2_2") (pintype "passive"))
      (node (ref "X3") (pin "3") (pinfunction "S_3") (pintype "passive"))
    )
    (net (code "27") (name "GND") (class "Default")
      (node (ref "C1") (pin "2") (pinfunction "2_2") (pintype "passive"))
      (node (ref "C2") (pin "2") (pinfunction "2_2") (pintype "passive"))
      (node (ref "C3") (pin "2") (pinfunction "2_2") (pintype "passive"))
      (node (ref "C4") (pin "2") (pinfunction "2_2") (pintype "passive"))
      (node (ref "IC1") (pin "2") (pinfunction "GND_2") (pintype "passive"))
      (node (ref "J1") (pin "3") (pinfunction "3_3") (pintype "passive"))
      (node (ref "JMP3") (pin "3") (pinfunction "3_3") (pintype "passive"))
      (node (ref "JMP4") (pin "3") (pinfunction "3_3") (pintype "passive"))
      (node (ref "Q17") (pin "S") (pinfunction "S_S") (pintype "passive"))
      (node (ref "Q18") (pin "S") (pinfunction "S_S") (pintype "passive"))
      (node (ref "Q19") (pin "S") (pinfunction "S_S") (pintype "passive"))
      (node (ref "R11") (pin "1") (pinfunction "1_1") (pintype "passive"))
      (node (ref "R14") (pin "1") (pinfunction "1_1") (pintype "passive"))
      (node (ref "R17") (pin "1") (pinfunction "1_1") (pintype "passive"))
      (node (ref "R2") (pin "1") (pinfunction "1_1") (pintype "passive"))
      (node (ref "R20") (pin "1") (pinfunction "1_1") (pintype "passive"))
      (node (ref "R23") (pin "1") (pinfunction "1_1") (pintype "passive"))
      (node (ref "R26") (pin "1") (pinfunction "1_1") (pintype "passive"))
      (node (ref "R29") (pin "1") (pinfunction "1_1") (pintype "passive"))
      (node (ref "R32") (pin "1") (pinfunction "1_1") (pintype "passive"))
      (node (ref "R35") (pin "1") (pinfunction "1_1") (pintype "passive"))
      (node (ref "R38") (pin "1") (pinfunction "1_1") (pintype "passive"))
      (node (ref "R41") (pin "1") (pinfunction "1_1") (pintype "passive"))
      (node (ref "R44") (pin "1") (pinfunction "1_1") (pintype "passive"))
      (node (ref "R47") (pin "1") (pinfunction "1_1") (pintype "passive"))
      (node (ref "R49") (pin "1") (pinfunction "1_1") (pintype "passive"))
      (node (ref "R5") (pin "1") (pinfunction "1_1") (pintype "passive"))
      (node (ref "R50") (pin "1") (pinfunction "1_1") (pintype "passive"))
      (node (ref "R51") (pin "1") (pinfunction "1_1") (pintype "passive"))
      (node (ref "R52") (pin "1") (pinfunction "1_1") (pintype "passive"))
      (node (ref "R53") (pin "1") (pinfunction "1_1") (pintype "passive"))
      (node (ref "R54") (pin "1") (pinfunction "1_1") (pintype "passive"))
      (node (ref "R55") (pin "1") (pinfunction "1_1") (pintype "passive"))
      (node (ref "R56") (pin "1") (pinfunction "1_1") (pintype "passive"))
      (node (ref "R57") (pin "1") (pinfunction "1_1") (pintype "passive"))
      (node (ref "R58") (pin "1") (pinfunction "1_1") (pintype "passive"))
      (node (ref "R59") (pin "1") (pinfunction "1_1") (pintype "passive"))
      (node (ref "R60") (pin "1") (pinfunction "1_1") (pintype "passive"))
      (node (ref "R61") (pin "1") (pinfunction "1_1") (pintype "passive"))
      (node (ref "R62") (pin "1") (pinfunction "1_1") (pintype "passive"))
      (node (ref "R63") (pin "1") (pinfunction "1_1") (pintype "passive"))
      (node (ref "R64") (pin "1") (pinfunction "1_1") (pintype "passive"))
      (node (ref "R65") (pin "1") (pinfunction "1_1") (pintype "passive"))
      (node (ref "R8") (pin "1") (pinfunction "1_1") (pintype "passive"))
      (node (ref "R80") (pin "2") (pinfunction "2_2") (pintype "passive"))
      (node (ref "R81") (pin "2") (pinfunction "2_2") (pintype "passive"))
      (node (ref "R82") (pin "1") (pinfunction "1_1") (pintype "passive"))
      (node (ref "R83") (pin "1") (pinfunction "1_1") (pintype "passive"))
      (node (ref "T1") (pin "3") (pinfunction "E_3") (pintype "passive"))
      (node (ref "T10") (pin "3") (pinfunction "E_3") (pintype "passive"))
      (node (ref "T11") (pin "3") (pinfunction "E_3") (pintype "passive"))
      (node (ref "T12") (pin "3") (pinfunction "E_3") (pintype "passive"))
      (node (ref "T13") (pin "3") (pinfunction "E_3") (pintype "passive"))
      (node (ref "T14") (pin "3") (pinfunction "E_3") (pintype "passive"))
      (node (ref "T15") (pin "3") (pinfunction "E_3") (pintype "passive"))
      (node (ref "T16") (pin "3") (pinfunction "E_3") (pintype "passive"))
      (node (ref "T2") (pin "3") (pinfunction "E_3") (pintype "passive"))
      (node (ref "T3") (pin "3") (pinfunction "E_3") (pintype "passive"))
      (node (ref "T4") (pin "3") (pinfunction "E_3") (pintype "passive"))
      (node (ref "T5") (pin "3") (pinfunction "E_3") (pintype "passive"))
      (node (ref "T6") (pin "3") (pinfunction "E_3") (pintype "passive"))
      (node (ref "T7") (pin "3") (pinfunction "E_3") (pintype "passive"))
      (node (ref "T8") (pin "3") (pinfunction "E_3") (pintype "passive"))
      (node (ref "T9") (pin "3") (pinfunction "E_3") (pintype "passive"))
      (node (ref "TEMP") (pin "1") (pinfunction "S_1") (pintype "passive"))
      (node (ref "U$1") (pin "14") (pinfunction "GND_14") (pintype "power_in"))
      (node (ref "U$1") (pin "20") (pinfunction "GND_20") (pintype "power_in"))
      (node (ref "U$1") (pin "25") (pinfunction "GND_25") (pintype "power_in"))
      (node (ref "U$1") (pin "30") (pinfunction "GND_30") (pintype "power_in"))
      (node (ref "U$1") (pin "34") (pinfunction "GND_34") (pintype "power_in"))
      (node (ref "U$1") (pin "39") (pinfunction "GND_39") (pintype "power_in"))
      (node (ref "U$1") (pin "6") (pinfunction "GND_6") (pintype "power_in"))
      (node (ref "U$1") (pin "9") (pinfunction "GND_9") (pintype "power_in"))
      (node (ref "U$2") (pin "12") (pinfunction "VSSA_12") (pintype "bidirectional"))
      (node (ref "U$2") (pin "18") (pinfunction "VSS_18") (pintype "bidirectional"))
      (node (ref "U$2") (pin "63") (pinfunction "VSS_63") (pintype "bidirectional"))
      (node (ref "U$21") (pin "2") (pinfunction "GND_2") (pintype "bidirectional"))
      (node (ref "U$21") (pin "6") (pinfunction "GND_6") (pintype "bidirectional"))
      (node (ref "U$3") (pin "3") (pinfunction "GND_3") (pintype "bidirectional"))
      (node (ref "X1") (pin "1") (pinfunction "1_1") (pintype "passive"))
      (node (ref "X2") (pin "1") (pinfunction "B_1") (pintype "passive"))
      (node (ref "X2") (pin "3") (pinfunction "B_3") (pintype "passive"))
      (node (ref "X2") (pin "5") (pinfunction "B_5") (pintype "passive"))
      (node (ref "X2") (pin "7") (pinfunction "B_7") (pintype "passive"))
      (node (ref "X2") (pin "9") (pinfunction "B_9") (pintype "passive"))
    )
    (net (code "28") (name "GSM_RST") (class "Default")
      (node (ref "U$1") (pin "15") (pinfunction "GPIO22/GEN3_15") (pintype "bidirectional"))
      (node (ref "U$21") (pin "7") (pinfunction "RST_7") (pintype "bidirectional"))
    )
    (net (code "29") (name "G_") (class "Default")
      (node (ref "R78") (pin "2") (pinfunction "2_2") (pintype "passive"))
      (node (ref "X4") (pin "3") (pinfunction "S_3") (pintype "passive"))
    )
    (net (code "30") (name "MS") (class "Default")
      (node (ref "U$2") (pin "46") (pinfunction "PA13_46") (pintype "bidirectional"))
      (node (ref "X2") (pin "2") (pinfunction "B_2") (pintype "passive"))
    )
    (net (code "31") (name "NRST") (class "Default")
      (node (ref "U$2") (pin "7") (pinfunction "NRST_7") (pintype "bidirectional"))
      (node (ref "X2") (pin "10") (pinfunction "B_10") (pintype "passive"))
    )
    (net (code "32") (name "Net-(D1A-CATHODE)") (class "Default")
      (node (ref "D1") (pin "K") (pinfunction "CATHODE_K") (pintype "bidirectional"))
      (node (ref "Q1") (pin "D") (pinfunction "D_D") (pintype "passive"))
    )
    (net (code "33") (name "Net-(D2A-CATHODE)") (class "Default")
      (node (ref "D2") (pin "K") (pinfunction "CATHODE_K") (pintype "bidirectional"))
      (node (ref "Q2") (pin "D") (pinfunction "D_D") (pintype "passive"))
    )
    (net (code "34") (name "Net-(D3A-CATHODE)") (class "Default")
      (node (ref "D3") (pin "K") (pinfunction "CATHODE_K") (pintype "bidirectional"))
      (node (ref "Q3") (pin "D") (pinfunction "D_D") (pintype "passive"))
    )
    (net (code "35") (name "Net-(D4A-CATHODE)") (class "Default")
      (node (ref "D4") (pin "K") (pinfunction "CATHODE_K") (pintype "bidirectional"))
      (node (ref "Q4") (pin "D") (pinfunction "D_D") (pintype "passive"))
    )
    (net (code "36") (name "Net-(D5A-CATHODE)") (class "Default")
      (node (ref "D5") (pin "K") (pinfunction "CATHODE_K") (pintype "bidirectional"))
      (node (ref "Q5") (pin "D") (pinfunction "D_D") (pintype "passive"))
    )
    (net (code "37") (name "Net-(D6A-CATHODE)") (class "Default")
      (node (ref "D6") (pin "K") (pinfunction "CATHODE_K") (pintype "bidirectional"))
      (node (ref "Q6") (pin "D") (pinfunction "D_D") (pintype "passive"))
    )
    (net (code "38") (name "Net-(D7A-CATHODE)") (class "Default")
      (node (ref "D7") (pin "K") (pinfunction "CATHODE_K") (pintype "bidirectional"))
      (node (ref "Q7") (pin "D") (pinfunction "D_D") (pintype "passive"))
    )
    (net (code "39") (name "Net-(D8A-CATHODE)") (class "Default")
      (node (ref "D8") (pin "K") (pinfunction "CATHODE_K") (pintype "bidirectional"))
      (node (ref "Q8") (pin "D") (pinfunction "D_D") (pintype "passive"))
    )
    (net (code "40") (name "Net-(D9A-CATHODE)") (class "Default")
      (node (ref "D9") (pin "K") (pinfunction "CATHODE_K") (pintype "bidirectional"))
      (node (ref "Q9") (pin "D") (pinfunction "D_D") (pintype "passive"))
    )
    (net (code "41") (name "Net-(D10A-CATHODE)") (class "Default")
      (node (ref "D10") (pin "K") (pinfunction "CATHODE_K") (pintype "bidirectional"))
      (node (ref "Q10") (pin "D") (pinfunction "D_D") (pintype "passive"))
    )
    (net (code "42") (name "Net-(D11A-CATHODE)") (class "Default")
      (node (ref "D11") (pin "K") (pinfunction "CATHODE_K") (pintype "bidirectional"))
      (node (ref "Q11") (pin "D") (pinfunction "D_D") (pintype "passive"))
    )
    (net (code "43") (name "Net-(D12A-CATHODE)") (class "Default")
      (node (ref "D12") (pin "K") (pinfunction "CATHODE_K") (pintype "bidirectional"))
      (node (ref "Q12") (pin "D") (pinfunction "D_D") (pintype "passive"))
    )
    (net (code "44") (name "Net-(D13A-CATHODE)") (class "Default")
      (node (ref "D13") (pin "K") (pinfunction "CATHODE_K") (pintype "bidirectional"))
      (node (ref "Q13") (pin "D") (pinfunction "D_D") (pintype "passive"))
    )
    (net (code "45") (name "Net-(D14A-CATHODE)") (class "Default")
      (node (ref "D14") (pin "K") (pinfunction "CATHODE_K") (pintype "bidirectional"))
      (node (ref "Q14") (pin "D") (pinfunction "D_D") (pintype "passive"))
    )
    (net (code "46") (name "Net-(D15A-CATHODE)") (class "Default")
      (node (ref "D15") (pin "K") (pinfunction "CATHODE_K") (pintype "bidirectional"))
      (node (ref "Q15") (pin "D") (pinfunction "D_D") (pintype "passive"))
    )
    (net (code "47") (name "Net-(D16A-CATHODE)") (class "Default")
      (node (ref "D16") (pin "K") (pinfunction "CATHODE_K") (pintype "bidirectional"))
      (node (ref "Q16") (pin "D") (pinfunction "D_D") (pintype "passive"))
    )
    (net (code "48") (name "Net-(D17-ANODE)") (class "Default")
      (node (ref "D17") (pin "A") (pinfunction "ANODE_A") (pintype "bidirectional"))
      (node (ref "U$1") (pin "38") (pinfunction "GPIO20_38") (pintype "bidirectional"))
    )
    (net (code "49") (name "Net-(D17-CATHODE)") (class "Default")
      (node (ref "D17") (pin "C") (pinfunction "CATHODE_C") (pintype "bidirectional"))
      (node (ref "R81") (pin "1") (pinfunction "1_1") (pintype "passive"))
    )
    (net (code "50") (name "Net-(D18-ANODE)") (class "Default")
      (node (ref "D18") (pin "A") (pinfunction "ANODE_A") (pintype "bidirectional"))
      (node (ref "U$2") (pin "33") (pinfunction "PB12_33") (pintype "bidirectional"))
    )
    (net (code "51") (name "Net-(D18-CATHODE)") (class "Default")
      (node (ref "D18") (pin "C") (pinfunction "CATHODE_C") (pintype "bidirectional"))
      (node (ref "R83") (pin "2") (pinfunction "2_2") (pintype "passive"))
    )
    (net (code "52") (name "Net-(D19-ANODE)") (class "Default")
      (node (ref "D19") (pin "A") (pinfunction "ANODE_A") (pintype "bidirectional"))
      (node (ref "U$1") (pin "36") (pinfunction "GPIO16_36") (pintype "bidirectional"))
    )
    (net (code "53") (name "Net-(D19-CATHODE)") (class "Default")
      (node (ref "D19") (pin "C") (pinfunction "CATHODE_C") (pintype "bidirectional"))
      (node (ref "R80") (pin "1") (pinfunction "1_1") (pintype "passive"))
    )
    (net (code "54") (name "Net-(FANB-S)") (class "Default")
      (node (ref "FAN") (pin "2") (pinfunction "S_2") (pintype "passive"))
      (node (ref "Q19") (pin "D") (pinfunction "D_D") (pintype "passive"))
    )
    (net (code "55") (name "Net-(PUMP0B-S)") (class "Default")
      (node (ref "PUMP0") (pin "2") (pinfunction "S_2") (pintype "passive"))
      (node (ref "Q17") (pin "D") (pinfunction "D_D") (pintype "passive"))
    )
    (net (code "56") (name "Net-(PUMP1B-S)") (class "Default")
      (node (ref "PUMP1") (pin "2") (pinfunction "S_2") (pintype "passive"))
      (node (ref "Q18") (pin "D") (pinfunction "D_D") (pintype "passive"))
    )
    (net (code "57") (name "Net-(T1-B)") (class "Default")
      (node (ref "Q1") (pin "S") (pinfunction "S_S") (pintype "passive"))
      (node (ref "R57") (pin "2") (pinfunction "2_2") (pintype "passive"))
      (node (ref "T1") (pin "2") (pinfunction "B_2") (pintype "passive"))
    )
    (net (code "58") (name "Net-(T2-B)") (class "Default")
      (node (ref "Q2") (pin "S") (pinfunction "S_S") (pintype "passive"))
      (node (ref "R58") (pin "2") (pinfunction "2_2") (pintype "passive"))
      (node (ref "T2") (pin "2") (pinfunction "B_2") (pintype "passive"))
    )
    (net (code "59") (name "Net-(T3-B)") (class "Default")
      (node (ref "Q3") (pin "S") (pinfunction "S_S") (pintype "passive"))
      (node (ref "R59") (pin "2") (pinfunction "2_2") (pintype "passive"))
      (node (ref "T3") (pin "2") (pinfunction "B_2") (pintype "passive"))
    )
    (net (code "60") (name "Net-(T4-B)") (class "Default")
      (node (ref "Q4") (pin "S") (pinfunction "S_S") (pintype "passive"))
      (node (ref "R60") (pin "2") (pinfunction "2_2") (pintype "passive"))
      (node (ref "T4") (pin "2") (pinfunction "B_2") (pintype "passive"))
    )
    (net (code "61") (name "Net-(T5-B)") (class "Default")
      (node (ref "Q5") (pin "S") (pinfunction "S_S") (pintype "passive"))
      (node (ref "R61") (pin "2") (pinfunction "2_2") (pintype "passive"))
      (node (ref "T5") (pin "2") (pinfunction "B_2") (pintype "passive"))
    )
    (net (code "62") (name "Net-(T6-B)") (class "Default")
      (node (ref "Q6") (pin "S") (pinfunction "S_S") (pintype "passive"))
      (node (ref "R62") (pin "2") (pinfunction "2_2") (pintype "passive"))
      (node (ref "T6") (pin "2") (pinfunction "B_2") (pintype "passive"))
    )
    (net (code "63") (name "Net-(T7-B)") (class "Default")
      (node (ref "Q7") (pin "S") (pinfunction "S_S") (pintype "passive"))
      (node (ref "R63") (pin "2") (pinfunction "2_2") (pintype "passive"))
      (node (ref "T7") (pin "2") (pinfunction "B_2") (pintype "passive"))
    )
    (net (code "64") (name "Net-(T8-B)") (class "Default")
      (node (ref "Q8") (pin "S") (pinfunction "S_S") (pintype "passive"))
      (node (ref "R64") (pin "2") (pinfunction "2_2") (pintype "passive"))
      (node (ref "T8") (pin "2") (pinfunction "B_2") (pintype "passive"))
    )
    (net (code "65") (name "Net-(T9-B)") (class "Default")
      (node (ref "Q9") (pin "S") (pinfunction "S_S") (pintype "passive"))
      (node (ref "R49") (pin "2") (pinfunction "2_2") (pintype "passive"))
      (node (ref "T9") (pin "2") (pinfunction "B_2") (pintype "passive"))
    )
    (net (code "66") (name "Net-(T10-B)") (class "Default")
      (node (ref "Q10") (pin "S") (pinfunction "S_S") (pintype "passive"))
      (node (ref "R50") (pin "2") (pinfunction "2_2") (pintype "passive"))
      (node (ref "T10") (pin "2") (pinfunction "B_2") (pintype "passive"))
    )
    (net (code "67") (name "Net-(T11-B)") (class "Default")
      (node (ref "Q11") (pin "S") (pinfunction "S_S") (pintype "passive"))
      (node (ref "R51") (pin "2") (pinfunction "2_2") (pintype "passive"))
      (node (ref "T11") (pin "2") (pinfunction "B_2") (pintype "passive"))
    )
    (net (code "68") (name "Net-(T12-B)") (class "Default")
      (node (ref "Q12") (pin "S") (pinfunction "S_S") (pintype "passive"))
      (node (ref "R52") (pin "2") (pinfunction "2_2") (pintype "passive"))
      (node (ref "T12") (pin "2") (pinfunction "B_2") (pintype "passive"))
    )
    (net (code "69") (name "Net-(T13-B)") (class "Default")
      (node (ref "Q13") (pin "S") (pinfunction "S_S") (pintype "passive"))
      (node (ref "R56") (pin "2") (pinfunction "2_2") (pintype "passive"))
      (node (ref "T13") (pin "2") (pinfunction "B_2") (pintype "passive"))
    )
    (net (code "70") (name "Net-(T14-B)") (class "Default")
      (node (ref "Q14") (pin "S") (pinfunction "S_S") (pintype "passive"))
      (node (ref "R55") (pin "2") (pinfunction "2_2") (pintype "passive"))
      (node (ref "T14") (pin "2") (pinfunction "B_2") (pintype "passive"))
    )
    (net (code "71") (name "Net-(T15-B)") (class "Default")
      (node (ref "Q15") (pin "S") (pinfunction "S_S") (pintype "passive"))
      (node (ref "R54") (pin "2") (pinfunction "2_2") (pintype "passive"))
      (node (ref "T15") (pin "2") (pinfunction "B_2") (pintype "passive"))
    )
    (net (code "72") (name "Net-(T16-B)") (class "Default")
      (node (ref "Q16") (pin "S") (pinfunction "S_S") (pintype "passive"))
      (node (ref "R53") (pin "2") (pinfunction "2_2") (pintype "passive"))
      (node (ref "T16") (pin "2") (pinfunction "B_2") (pintype "passive"))
    )
    (net (code "73") (name "Net-(TEMPB-S)") (class "Default")
      (node (ref "R71") (pin "2") (pinfunction "2_2") (pintype "passive"))
      (node (ref "TEMP") (pin "2") (pinfunction "S_2") (pintype "passive"))
      (node (ref "U$1") (pin "7") (pinfunction "GPIO4/GCKL_7") (pintype "bidirectional"))
    )
    (net (code "74") (name "Net-(U$1-GPIO2{slash}SDA1)") (class "Default")
      (node (ref "R73") (pin "1") (pinfunction "1_1") (pintype "passive"))
      (node (ref "U$1") (pin "3") (pinfunction "GPIO2/SDA1_3") (pintype "bidirectional"))
      (node (ref "U$3") (pin "2") (pinfunction "SDA_2") (pintype "bidirectional"))
    )
    (net (code "75") (name "Net-(U$1-GPIO3{slash}SCL1)") (class "Default")
      (node (ref "R72") (pin "2") (pinfunction "2_2") (pintype "passive"))
      (node (ref "U$1") (pin "5") (pinfunction "GPIO3/SCL1_5") (pintype "bidirectional"))
      (node (ref "U$3") (pin "4") (pinfunction "SCL_4") (pintype "bidirectional"))
    )
    (net (code "76") (name "Net-(U$2-VCAP_1)") (class "Default")
      (node (ref "C3") (pin "1") (pinfunction "1_1") (pintype "passive"))
      (node (ref "U$2") (pin "31") (pinfunction "VCAP_1_31") (pintype "bidirectional"))
    )
    (net (code "77") (name "Net-(U$2-VCAP_2)") (class "Default")
      (node (ref "C4") (pin "1") (pinfunction "1_1") (pintype "passive"))
      (node (ref "U$2") (pin "47") (pinfunction "VCAP_2_47") (pintype "bidirectional"))
    )
    (net (code "78") (name "Net-(X1C-1)") (class "Default")
      (node (ref "R66") (pin "2") (pinfunction "2_2") (pintype "passive"))
      (node (ref "X1") (pin "3") (pinfunction "1_3") (pintype "passive"))
    )
    (net (code "79") (name "Net-(X1D-1)") (class "Default")
      (node (ref "JMP1") (pin "2") (pinfunction "2_2") (pintype "passive"))
      (node (ref "R66") (pin "1") (pinfunction "1_1") (pintype "passive"))
      (node (ref "X1") (pin "4") (pinfunction "1_4") (pintype "passive"))
    )
    (net (code "80") (name "Net-(X3B-S)") (class "Default")
      (node (ref "JMP3") (pin "2") (pinfunction "2_2") (pintype "passive"))
      (node (ref "X3") (pin "2") (pinfunction "S_2") (pintype "passive"))
    )
    (net (code "81") (name "Net-(X4B-S)") (class "Default")
      (node (ref "JMP4") (pin "2") (pinfunction "2_2") (pintype "passive"))
      (node (ref "X4") (pin "2") (pinfunction "S_2") (pintype "passive"))
    )
    (net (code "82") (name "Net-(X5A-S)") (class "Default")
      (node (ref "JMP2") (pin "2") (pinfunction "2_2") (pintype "passive"))
      (node (ref "X5") (pin "1") (pinfunction "S_1") (pintype "passive"))
    )
    (net (code "83") (name "P0") (class "Default")
      (node (ref "Q17") (pin "G") (pinfunction "G_G") (pintype "passive"))
      (node (ref "R68") (pin "1") (pinfunction "1_1") (pintype "passive"))
      (node (ref "U$1") (pin "32") (pinfunction "GPIO12_32") (pintype "bidirectional"))
    )
    (net (code "84") (name "P1") (class "Default")
      (node (ref "Q18") (pin "G") (pinfunction "G_G") (pintype "passive"))
      (node (ref "R69") (pin "1") (pinfunction "1_1") (pintype "passive"))
      (node (ref "U$1") (pin "28") (pinfunction "ID_SC_28") (pintype "bidirectional"))
    )
    (net (code "85") (name "PI_3V3") (class "Default")
      (node (ref "JMP1") (pin "3") (pinfunction "3_3") (pintype "passive"))
      (node (ref "JMP4") (pin "1") (pinfunction "1_1") (pintype "passive"))
      (node (ref "R71") (pin "1") (pinfunction "1_1") (pintype "passive"))
      (node (ref "R72") (pin "1") (pinfunction "1_1") (pintype "passive"))
      (node (ref "R73") (pin "2") (pinfunction "2_2") (pintype "passive"))
      (node (ref "TEMP") (pin "3") (pinfunction "S_3") (pintype "passive"))
      (node (ref "U$1") (pin "1") (pinfunction "3V3_1") (pintype "power_in"))
      (node (ref "U$3") (pin "1") (pinfunction "VDD_1") (pintype "bidirectional"))
    )
    (net (code "86") (name "PI_3V3_2") (class "Default")
      (node (ref "JMP2") (pin "3") (pinfunction "3_3") (pintype "passive"))
      (node (ref "U$1") (pin "17") (pinfunction "3V3_17") (pintype "power_in"))
    )
    (net (code "87") (name "PI_B") (class "Default")
      (node (ref "R79") (pin "1") (pinfunction "1_1") (pintype "passive"))
      (node (ref "U$1") (pin "16") (pinfunction "GEN4/GPIO23_16") (pintype "bidirectional"))
    )
    (net (code "88") (name "PI_G") (class "Default")
      (node (ref "R78") (pin "1") (pinfunction "1_1") (pintype "passive"))
      (node (ref "U$1") (pin "18") (pinfunction "GEN5/GPIO24_18") (pintype "bidirectional"))
    )
    (net (code "89") (name "PI_R") (class "Default")
      (node (ref "R77") (pin "1") (pinfunction "1_1") (pintype "passive"))
      (node (ref "U$1") (pin "22") (pinfunction "GEN/6GPIO25_22") (pintype "bidirectional"))
    )
    (net (code "90") (name "PI_RX") (class "Default")
      (node (ref "U$1") (pin "11") (pinfunction "GPIO17/GEN0_11") (pintype "bidirectional"))
      (node (ref "U$21") (pin "4") (pinfunction "TXD_4") (pintype "bidirectional"))
    )
    (net (code "91") (name "PI_STM32_0") (class "Default")
      (node (ref "U$1") (pin "24") (pinfunction "~{CE0}/GPIO8_24") (pintype "bidirectional"))
      (node (ref "U$2") (pin "45") (pinfunction "PA12_45") (pintype "bidirectional"))
    )
    (net (code "92") (name "PI_STM32_1") (class "Default")
      (node (ref "U$1") (pin "26") (pinfunction "~{CE}/GPIO7_26") (pintype "bidirectional"))
      (node (ref "U$2") (pin "51") (pinfunction "PC10_51") (pintype "bidirectional"))
    )
    (net (code "93") (name "PI_TX") (class "Default")
      (node (ref "U$1") (pin "13") (pinfunction "GPIO27/GEN2_13") (pintype "bidirectional"))
      (node (ref "U$21") (pin "5") (pinfunction "RXD_5") (pintype "bidirectional"))
    )
    (net (code "94") (name "R") (class "Default")
      (node (ref "R74") (pin "2") (pinfunction "2_2") (pintype "passive"))
      (node (ref "X3") (pin "1") (pinfunction "S_1") (pintype "passive"))
    )
    (net (code "95") (name "R_") (class "Default")
      (node (ref "R77") (pin "2") (pinfunction "2_2") (pintype "passive"))
      (node (ref "X4") (pin "1") (pinfunction "S_1") (pintype "passive"))
    )
    (net (code "96") (name "SPILL_SENSE") (class "Default")
      (node (ref "R82") (pin "2") (pinfunction "2_2") (pintype "passive"))
      (node (ref "U$1") (pin "40") (pinfunction "GPIO21_40") (pintype "bidirectional"))
      (node (ref "X5") (pin "2") (pinfunction "S_2") (pintype "passive"))
    )
    (net (code "97") (name "STM32_B") (class "Default")
      (node (ref "R76") (pin "1") (pinfunction "1_1") (pintype "passive"))
      (node (ref "U$2") (pin "34") (pinfunction "PB13_34") (pintype "bidirectional"))
    )
    (net (code "98") (name "STM32_G") (class "Default")
      (node (ref "R75") (pin "1") (pinfunction "1_1") (pintype "passive"))
      (node (ref "U$2") (pin "35") (pinfunction "PB14_35") (pintype "bidirectional"))
    )
    (net (code "99") (name "STM32_R") (class "Default")
      (node (ref "R74") (pin "1") (pinfunction "1_1") (pintype "passive"))
      (node (ref "U$2") (pin "36") (pinfunction "PB15_36") (pintype "bidirectional"))
    )
    (net (code "100") (name "STM32_RX") (class "Default")
      (node (ref "U$1") (pin "8") (pinfunction "TXD0/GPIO14_8") (pintype "bidirectional"))
      (node (ref "U$2") (pin "54") (pinfunction "PD2_54") (pintype "bidirectional"))
    )
    (net (code "101") (name "STM32_TX") (class "Default")
      (node (ref "U$1") (pin "10") (pinfunction "RXD0/GPIO15_10") (pintype "bidirectional"))
      (node (ref "U$2") (pin "53") (pinfunction "PC12_53") (pintype "bidirectional"))
    )
    (net (code "102") (name "TEMP_D1") (class "Default")
      (node (ref "R41") (pin "2") (pinfunction "2_2") (pintype "passive"))
      (node (ref "R42") (pin "1") (pinfunction "1_1") (pintype "passive"))
      (node (ref "U$2") (pin "24") (pinfunction "PC4_24") (pintype "bidirectional"))
    )
    (net (code "103") (name "TEMP_D2") (class "Default")
      (node (ref "R8") (pin "2") (pinfunction "2_2") (pintype "passive"))
      (node (ref "R9") (pin "1") (pinfunction "1_1") (pintype "passive"))
      (node (ref "U$2") (pin "25") (pinfunction "PC5_25") (pintype "bidirectional"))
    )
    (net (code "104") (name "TEMP_D3") (class "Default")
      (node (ref "R14") (pin "2") (pinfunction "2_2") (pintype "passive"))
      (node (ref "R15") (pin "1") (pinfunction "1_1") (pintype "passive"))
      (node (ref "U$2") (pin "27") (pinfunction "PB1_27") (pintype "bidirectional"))
    )
    (net (code "105") (name "TEMP_D4") (class "Default")
      (node (ref "R17") (pin "2") (pinfunction "2_2") (pintype "passive"))
      (node (ref "R18") (pin "1") (pinfunction "1_1") (pintype "passive"))
      (node (ref "U$2") (pin "26") (pinfunction "PB0_26") (pintype "bidirectional"))
    )
    (net (code "106") (name "TEMP_D5") (class "Default")
      (node (ref "R44") (pin "2") (pinfunction "2_2") (pintype "passive"))
      (node (ref "R45") (pin "1") (pinfunction "1_1") (pintype "passive"))
      (node (ref "U$2") (pin "23") (pinfunction "PA7_23") (pintype "bidirectional"))
    )
    (net (code "107") (name "TEMP_D6") (class "Default")
      (node (ref "R47") (pin "2") (pinfunction "2_2") (pintype "passive"))
      (node (ref "R48") (pin "1") (pinfunction "1_1") (pintype "passive"))
      (node (ref "U$2") (pin "20") (pinfunction "PA4_20") (pintype "bidirectional"))
    )
    (net (code "108") (name "TEMP_D7") (class "Default")
      (node (ref "R11") (pin "2") (pinfunction "2_2") (pintype "passive"))
      (node (ref "R12") (pin "1") (pinfunction "1_1") (pintype "passive"))
      (node (ref "U$2") (pin "21") (pinfunction "PA5_21") (pintype "bidirectional"))
    )
    (net (code "109") (name "TEMP_D8") (class "Default")
      (node (ref "R20") (pin "2") (pinfunction "2_2") (pintype "passive"))
      (node (ref "R21") (pin "1") (pinfunction "1_1") (pintype "passive"))
      (node (ref "U$2") (pin "22") (pinfunction "PA6_22") (pintype "bidirectional"))
    )
    (net (code "110") (name "TEMP_D9") (class "Default")
      (node (ref "R32") (pin "2") (pinfunction "2_2") (pintype "passive"))
      (node (ref "R33") (pin "1") (pinfunction "1_1") (pintype "passive"))
      (node (ref "U$2") (pin "16") (pinfunction "PA2_16") (pintype "bidirectional"))
    )
    (net (code "111") (name "TEMP_D10") (class "Default")
      (node (ref "R29") (pin "2") (pinfunction "2_2") (pintype "passive"))
      (node (ref "R30") (pin "1") (pinfunction "1_1") (pintype "passive"))
      (node (ref "U$2") (pin "15") (pinfunction "PA1_15") (pintype "bidirectional"))
    )
    (net (code "112") (name "TEMP_D11") (class "Default")
      (node (ref "R26") (pin "2") (pinfunction "2_2") (pintype "passive"))
      (node (ref "R27") (pin "1") (pinfunction "1_1") (pintype "passive"))
      (node (ref "U$2") (pin "17") (pinfunction "PA3_17") (pintype "bidirectional"))
    )
    (net (code "113") (name "TEMP_D12") (class "Default")
      (node (ref "R23") (pin "2") (pinfunction "2_2") (pintype "passive"))
      (node (ref "R24") (pin "1") (pinfunction "1_1") (pintype "passive"))
      (node (ref "U$2") (pin "14") (pinfunction "PA0_14") (pintype "bidirectional"))
    )
    (net (code "114") (name "TEMP_D13") (class "Default")
      (node (ref "R5") (pin "2") (pinfunction "2_2") (pintype "passive"))
      (node (ref "R6") (pin "1") (pinfunction "1_1") (pintype "passive"))
      (node (ref "U$2") (pin "9") (pinfunction "PC1_9") (pintype "bidirectional"))
    )
    (net (code "115") (name "TEMP_D14") (class "Default")
      (node (ref "R35") (pin "2") (pinfunction "2_2") (pintype "passive"))
      (node (ref "R36") (pin "1") (pinfunction "1_1") (pintype "passive"))
      (node (ref "U$2") (pin "8") (pinfunction "PC0_8") (pintype "bidirectional"))
    )
    (net (code "116") (name "TEMP_D15") (class "Default")
      (node (ref "R38") (pin "2") (pinfunction "2_2") (pintype "passive"))
      (node (ref "R39") (pin "1") (pinfunction "1_1") (pintype "passive"))
      (node (ref "U$2") (pin "10") (pinfunction "PC2_10") (pintype "bidirectional"))
    )
    (net (code "117") (name "TEMP_D16") (class "Default")
      (node (ref "R2") (pin "2") (pinfunction "2_2") (pintype "passive"))
      (node (ref "R3") (pin "1") (pinfunction "1_1") (pintype "passive"))
      (node (ref "U$2") (pin "11") (pinfunction "PC3_11") (pintype "bidirectional"))
    )
    (net (code "118") (name "THERM_D1") (class "Default")
      (node (ref "D1") (pin "THERMAL") (pinfunction "P$1_THERMAL") (pintype "bidirectional"))
    )
    (net (code "119") (name "THERM_D2") (class "Default")
      (node (ref "D2") (pin "THERMAL") (pinfunction "P$1_THERMAL") (pintype "bidirectional"))
    )
    (net (code "120") (name "THERM_D3") (class "Default")
      (node (ref "D3") (pin "THERMAL") (pinfunction "P$1_THERMAL") (pintype "bidirectional"))
    )
    (net (code "121") (name "THERM_D4") (class "Default")
      (node (ref "D4") (pin "THERMAL") (pinfunction "P$1_THERMAL") (pintype "bidirectional"))
    )
    (net (code "122") (name "THERM_D5") (class "Default")
      (node (ref "D5") (pin "THERMAL") (pinfunction "P$1_THERMAL") (pintype "bidirectional"))
    )
    (net (code "123") (name "THERM_D6") (class "Default")
      (node (ref "D6") (pin "THERMAL") (pinfunction "P$1_THERMAL") (pintype "bidirectional"))
    )
    (net (code "124") (name "THERM_D7") (class "Default")
      (node (ref "D7") (pin "THERMAL") (pinfunction "P$1_THERMAL") (pintype "bidirectional"))
    )
    (net (code "125") (name "THERM_D8") (class "Default")
      (node (ref "D8") (pin "THERMAL") (pinfunction "P$1_THERMAL") (pintype "bidirectional"))
    )
    (net (code "126") (name "THERM_D9") (class "Default")
      (node (ref "D9") (pin "THERMAL") (pinfunction "P$1_THERMAL") (pintype "bidirectional"))
    )
    (net (code "127") (name "THERM_D10") (class "Default")
      (node (ref "D10") (pin "THERMAL") (pinfunction "P$1_THERMAL") (pintype "bidirectional"))
    )
    (net (code "128") (name "THERM_D11") (class "Default")
      (node (ref "D11") (pin "THERMAL") (pinfunction "P$1_THERMAL") (pintype "bidirectional"))
    )
    (net (code "129") (name "THERM_D12") (class "Default")
      (node (ref "D12") (pin "THERMAL") (pinfunction "P$1_THERMAL") (pintype "bidirectional"))
    )
    (net (code "130") (name "THERM_D13") (class "Default")
      (node (ref "D13") (pin "THERMAL") (pinfunction "P$1_THERMAL") (pintype "bidirectional"))
    )
    (net (code "131") (name "THERM_D14") (class "Default")
      (node (ref "D14") (pin "THERMAL") (pinfunction "P$1_THERMAL") (pintype "bidirectional"))
    )
    (net (code "132") (name "THERM_D15") (class "Default")
      (node (ref "D15") (pin "THERMAL") (pinfunction "P$1_THERMAL") (pintype "bidirectional"))
    )
    (net (code "133") (name "THERM_D16") (class "Default")
      (node (ref "D16") (pin "THERMAL") (pinfunction "P$1_THERMAL") (pintype "bidirectional"))
    )
    (net (code "134") (name "TOP_OFF") (class "Default")
      (node (ref "R65") (pin "2") (pinfunction "2_2") (pintype "passive"))
      (node (ref "R67") (pin "1") (pinfunction "1_1") (pintype "passive"))
      (node (ref "U$1") (pin "12") (pinfunction "GPIO18_12") (pintype "bidirectional"))
      (node (ref "X1") (pin "2") (pinfunction "1_2") (pintype "passive"))
    )
    (net (code "135") (name "VCC") (class "Default")
      (node (ref "C2") (pin "1") (pinfunction "1_1") (pintype "passive"))
      (node (ref "D1") (pin "A") (pinfunction "ANODE_A") (pintype "bidirectional"))
      (node (ref "D10") (pin "A") (pinfunction "ANODE_A") (pintype "bidirectional"))
      (node (ref "D11") (pin "A") (pinfunction "ANODE_A") (pintype "bidirectional"))
      (node (ref "D12") (pin "A") (pinfunction "ANODE_A") (pintype "bidirectional"))
      (node (ref "D13") (pin "A") (pinfunction "ANODE_A") (pintype "bidirectional"))
      (node (ref "D14") (pin "A") (pinfunction "ANODE_A") (pintype "bidirectional"))
      (node (ref "D15") (pin "A") (pinfunction "ANODE_A") (pintype "bidirectional"))
      (node (ref "D16") (pin "A") (pinfunction "ANODE_A") (pintype "bidirectional"))
      (node (ref "D2") (pin "A") (pinfunction "ANODE_A") (pintype "bidirectional"))
      (node (ref "D3") (pin "A") (pinfunction "ANODE_A") (pintype "bidirectional"))
      (node (ref "D4") (pin "A") (pinfunction "ANODE_A") (pintype "bidirectional"))
      (node (ref "D5") (pin "A") (pinfunction "ANODE_A") (pintype "bidirectional"))
      (node (ref "D6") (pin "A") (pinfunction "ANODE_A") (pintype "bidirectional"))
      (node (ref "D7") (pin "A") (pinfunction "ANODE_A") (pintype "bidirectional"))
      (node (ref "D8") (pin "A") (pinfunction "ANODE_A") (pintype "bidirectional"))
      (node (ref "D9") (pin "A") (pinfunction "ANODE_A") (pintype "bidirectional"))
      (node (ref "FAN") (pin "1") (pinfunction "S_1") (pintype "passive"))
      (node (ref "IC1") (pin "1") (pinfunction "VI_1") (pintype "input"))
      (node (ref "J1") (pin "1") (pinfunction "1_1") (pintype "passive"))
      (node (ref "JMP1") (pin "1") (pinfunction "1_1") (pintype "passive"))
      (node (ref "JMP2") (pin "1") (pinfunction "1_1") (pintype "passive"))
      (node (ref "PUMP0") (pin "1") (pinfunction "S_1") (pintype "passive"))
      (node (ref "PUMP1") (pin "1") (pinfunction "S_1") (pintype "passive"))
      (node (ref "R1") (pin "2") (pinfunction "2_2") (pintype "passive"))
      (node (ref "R10") (pin "2") (pinfunction "2_2") (pintype "passive"))
      (node (ref "R13") (pin "2") (pinfunction "2_2") (pintype "passive"))
      (node (ref "R16") (pin "2") (pinfunction "2_2") (pintype "passive"))
      (node (ref "R19") (pin "2") (pinfunction "2_2") (pintype "passive"))
      (node (ref "R22") (pin "2") (pinfunction "2_2") (pintype "passive"))
      (node (ref "R25") (pin "2") (pinfunction "2_2") (pintype "passive"))
      (node (ref "R28") (pin "2") (pinfunction "2_2") (pintype "passive"))
      (node (ref "R31") (pin "2") (pinfunction "2_2") (pintype "passive"))
      (node (ref "R34") (pin "2") (pinfunction "2_2") (pintype "passive"))
      (node (ref "R37") (pin "2") (pinfunction "2_2") (pintype "passive"))
      (node (ref "R4") (pin "2") (pinfunction "2_2") (pintype "passive"))
      (node (ref "R40") (pin "2") (pinfunction "2_2") (pintype "passive"))
      (node (ref "R43") (pin "2") (pinfunction "2_2") (pintype "passive"))
      (node (ref "R46") (pin "2") (pinfunction "2_2") (pintype "passive"))
      (node (ref "R67") (pin "2") (pinfunction "2_2") (pintype "passive"))
      (node (ref "R68") (pin "2") (pinfunction "2_2") (pintype "passive"))
      (node (ref "R69") (pin "2") (pinfunction "2_2") (pintype "passive"))
      (node (ref "R7") (pin "2") (pinfunction "2_2") (pintype "passive"))
      (node (ref "R70") (pin "2") (pinfunction "2_2") (pintype "passive"))
      (node (ref "U$1") (pin "2") (pinfunction "5V0_2") (pintype "power_in"))
      (node (ref "U$1") (pin "4") (pinfunction "5V0_4") (pintype "power_in"))
      (node (ref "U$21") (pin "1") (pinfunction "5V_1") (pintype "bidirectional"))
      (node (ref "U$21") (pin "3") (pinfunction "VDD_3") (pintype "bidirectional"))
    )
    (net (code "136") (name "unconnected-(J1-Pad2)") (class "Default")
      (node (ref "J1") (pin "2") (pinfunction "2_2") (pintype "passive"))
    )
    (net (code "137") (name "unconnected-(U$1-GPIO5-Pad29)") (class "Default")
      (node (ref "U$1") (pin "29") (pinfunction "GPIO5_29") (pintype "bidirectional"))
    )
    (net (code "138") (name "unconnected-(U$1-GPIO6-Pad31)") (class "Default")
      (node (ref "U$1") (pin "31") (pinfunction "GPIO6_31") (pintype "bidirectional"))
    )
    (net (code "139") (name "unconnected-(U$1-GPIO9{slash}MISO-Pad21)") (class "Default")
      (node (ref "U$1") (pin "21") (pinfunction "GPIO9/MISO_21") (pintype "bidirectional"))
    )
    (net (code "140") (name "unconnected-(U$1-GPIO10{slash}MOSI-Pad19)") (class "Default")
      (node (ref "U$1") (pin "19") (pinfunction "GPIO10/MOSI_19") (pintype "bidirectional"))
    )
    (net (code "141") (name "unconnected-(U$1-GPIO11{slash}SCLK-Pad23)") (class "Default")
      (node (ref "U$1") (pin "23") (pinfunction "GPIO11/SCLK_23") (pintype "bidirectional"))
    )
    (net (code "142") (name "unconnected-(U$1-GPIO13-Pad33)") (class "Default")
      (node (ref "U$1") (pin "33") (pinfunction "GPIO13_33") (pintype "bidirectional"))
    )
    (net (code "143") (name "unconnected-(U$1-GPIO19-Pad35)") (class "Default")
      (node (ref "U$1") (pin "35") (pinfunction "GPIO19_35") (pintype "bidirectional"))
    )
    (net (code "144") (name "unconnected-(U$1-GPIO26-Pad37)") (class "Default")
      (node (ref "U$1") (pin "37") (pinfunction "GPIO26_37") (pintype "bidirectional"))
    )
    (net (code "145") (name "unconnected-(U$1-ID_SD-Pad27)") (class "Default")
      (node (ref "U$1") (pin "27") (pinfunction "ID_SD_27") (pintype "bidirectional"))
    )
    (net (code "146") (name "unconnected-(U$2-BOOT0-Pad60)") (class "Default")
      (node (ref "U$2") (pin "60") (pinfunction "BOOT0_60") (pintype "bidirectional"))
    )
    (net (code "147") (name "unconnected-(U$2-PB2-Pad28)") (class "Default")
      (node (ref "U$2") (pin "28") (pinfunction "PB2_28") (pintype "bidirectional"))
    )
    (net (code "148") (name "unconnected-(U$2-PC11-Pad52)") (class "Default")
      (node (ref "U$2") (pin "52") (pinfunction "PC11_52") (pintype "bidirectional"))
    )
    (net (code "149") (name "unconnected-(U$2-PC14-Pad3)") (class "Default")
      (node (ref "U$2") (pin "3") (pinfunction "PC14_3") (pintype "bidirectional"))
    )
    (net (code "150") (name "unconnected-(U$2-PC15-Pad4)") (class "Default")
      (node (ref "U$2") (pin "4") (pinfunction "PC15_4") (pintype "bidirectional"))
    )
    (net (code "151") (name "unconnected-(U$2-PH0-Pad5)") (class "Default")
      (node (ref "U$2") (pin "5") (pinfunction "PH0_5") (pintype "bidirectional"))
    )
    (net (code "152") (name "unconnected-(U$2-PH1-Pad6)") (class "Default")
      (node (ref "U$2") (pin "6") (pinfunction "PH1_6") (pintype "bidirectional"))
    )
    (net (code "153") (name "unconnected-(U$2-VBAT-Pad1)") (class "Default")
      (node (ref "U$2") (pin "1") (pinfunction "VBAT_1") (pintype "bidirectional"))
    )
  )
)
